# chanomele_main.net
KiCad netlist of a schematic drawn in EAGLE
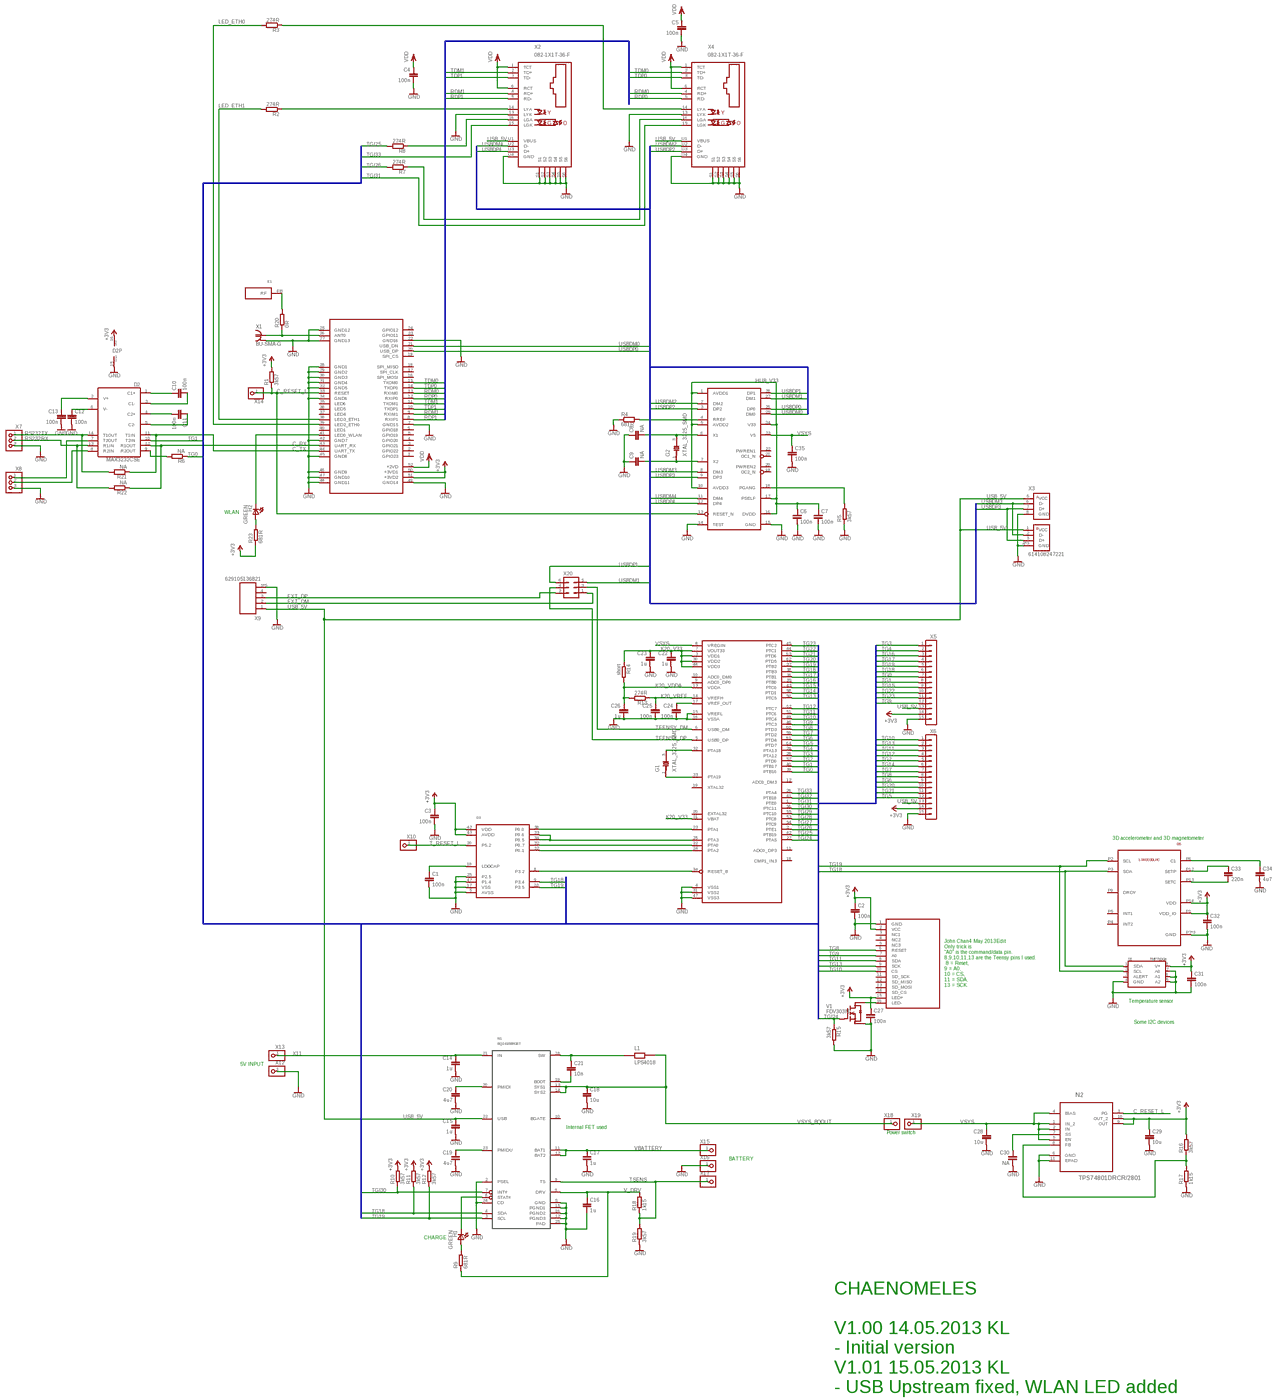
[diagram p0: schematic, sheet 1, overview]
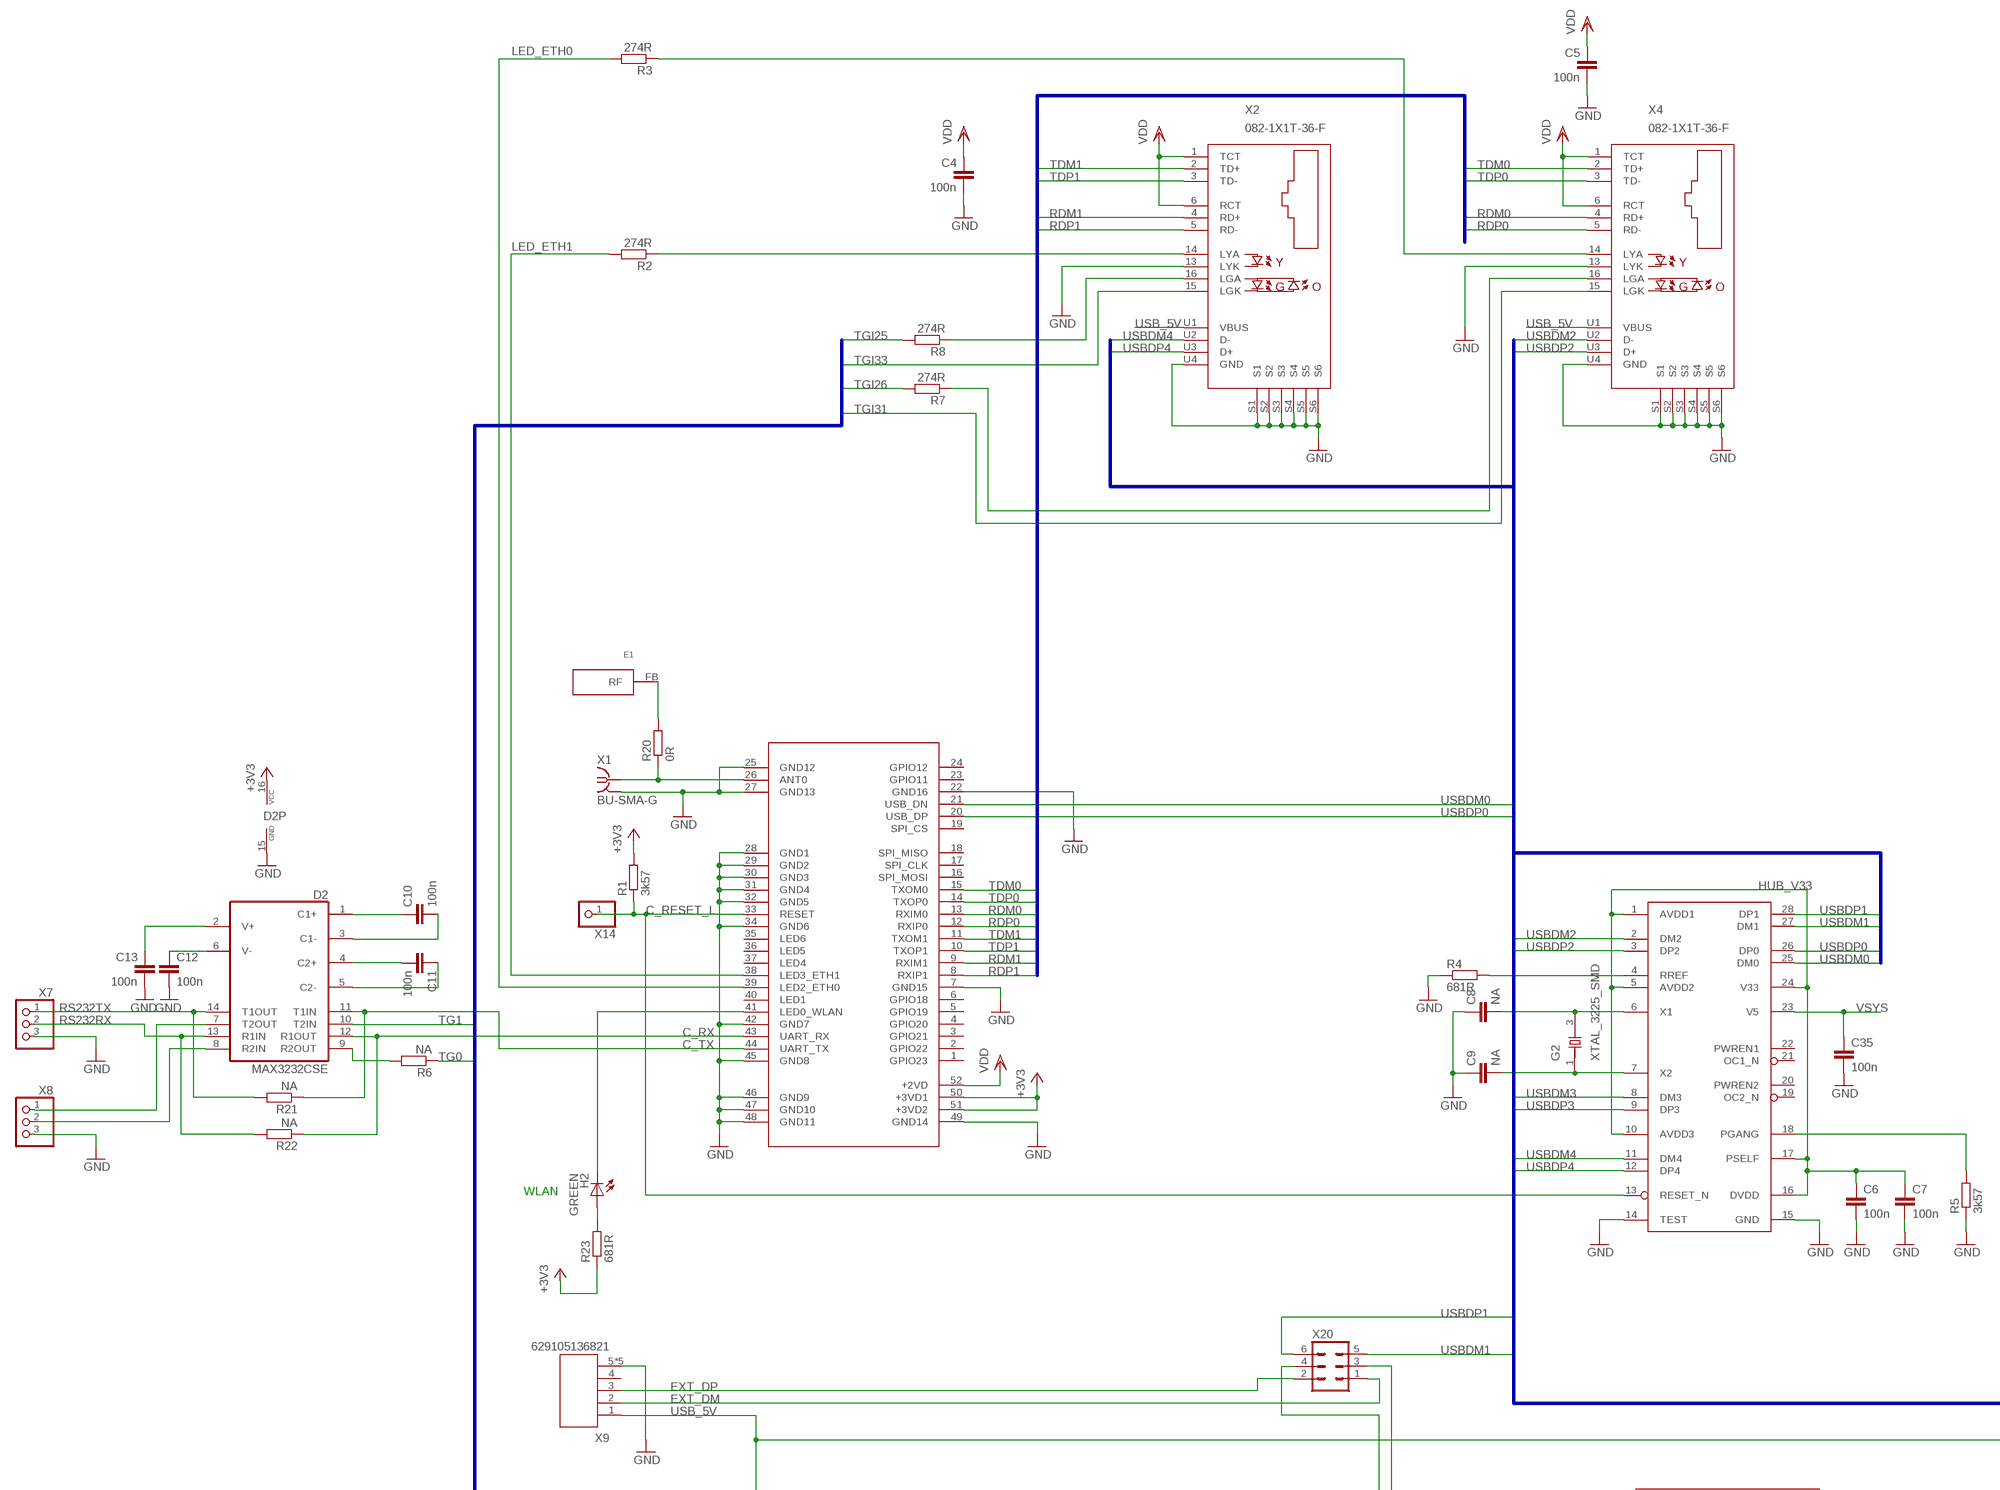
[diagram p1: schematic, sheet 1, part 1 of 4]
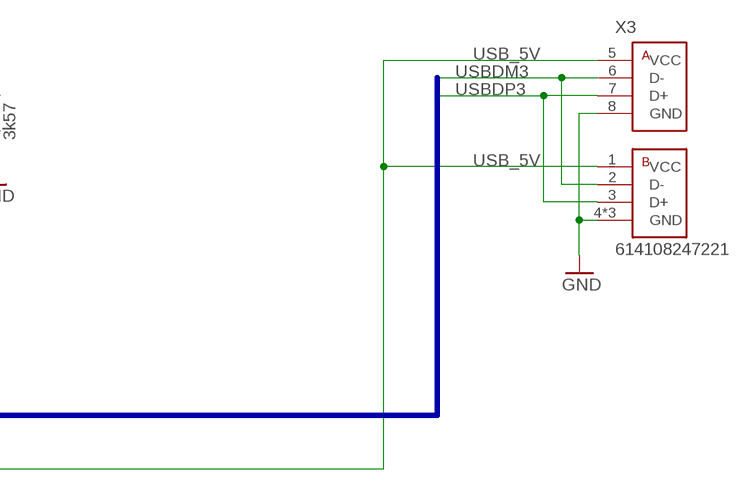
[diagram p2: schematic, sheet 1, part 2 of 4]
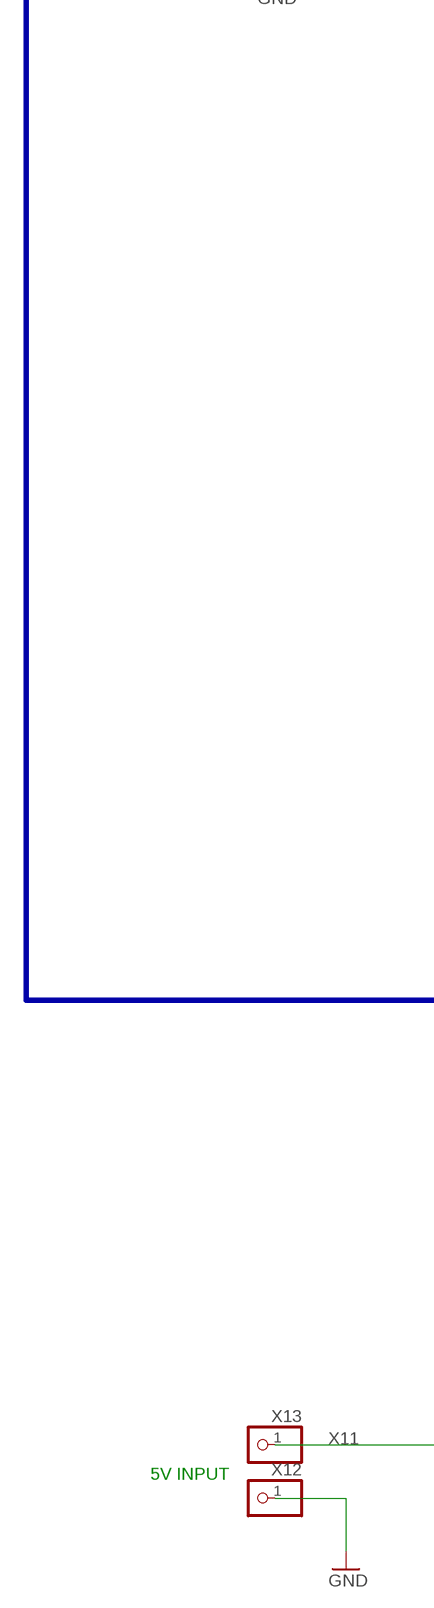
[diagram p3: schematic, sheet 1, part 3 of 4]
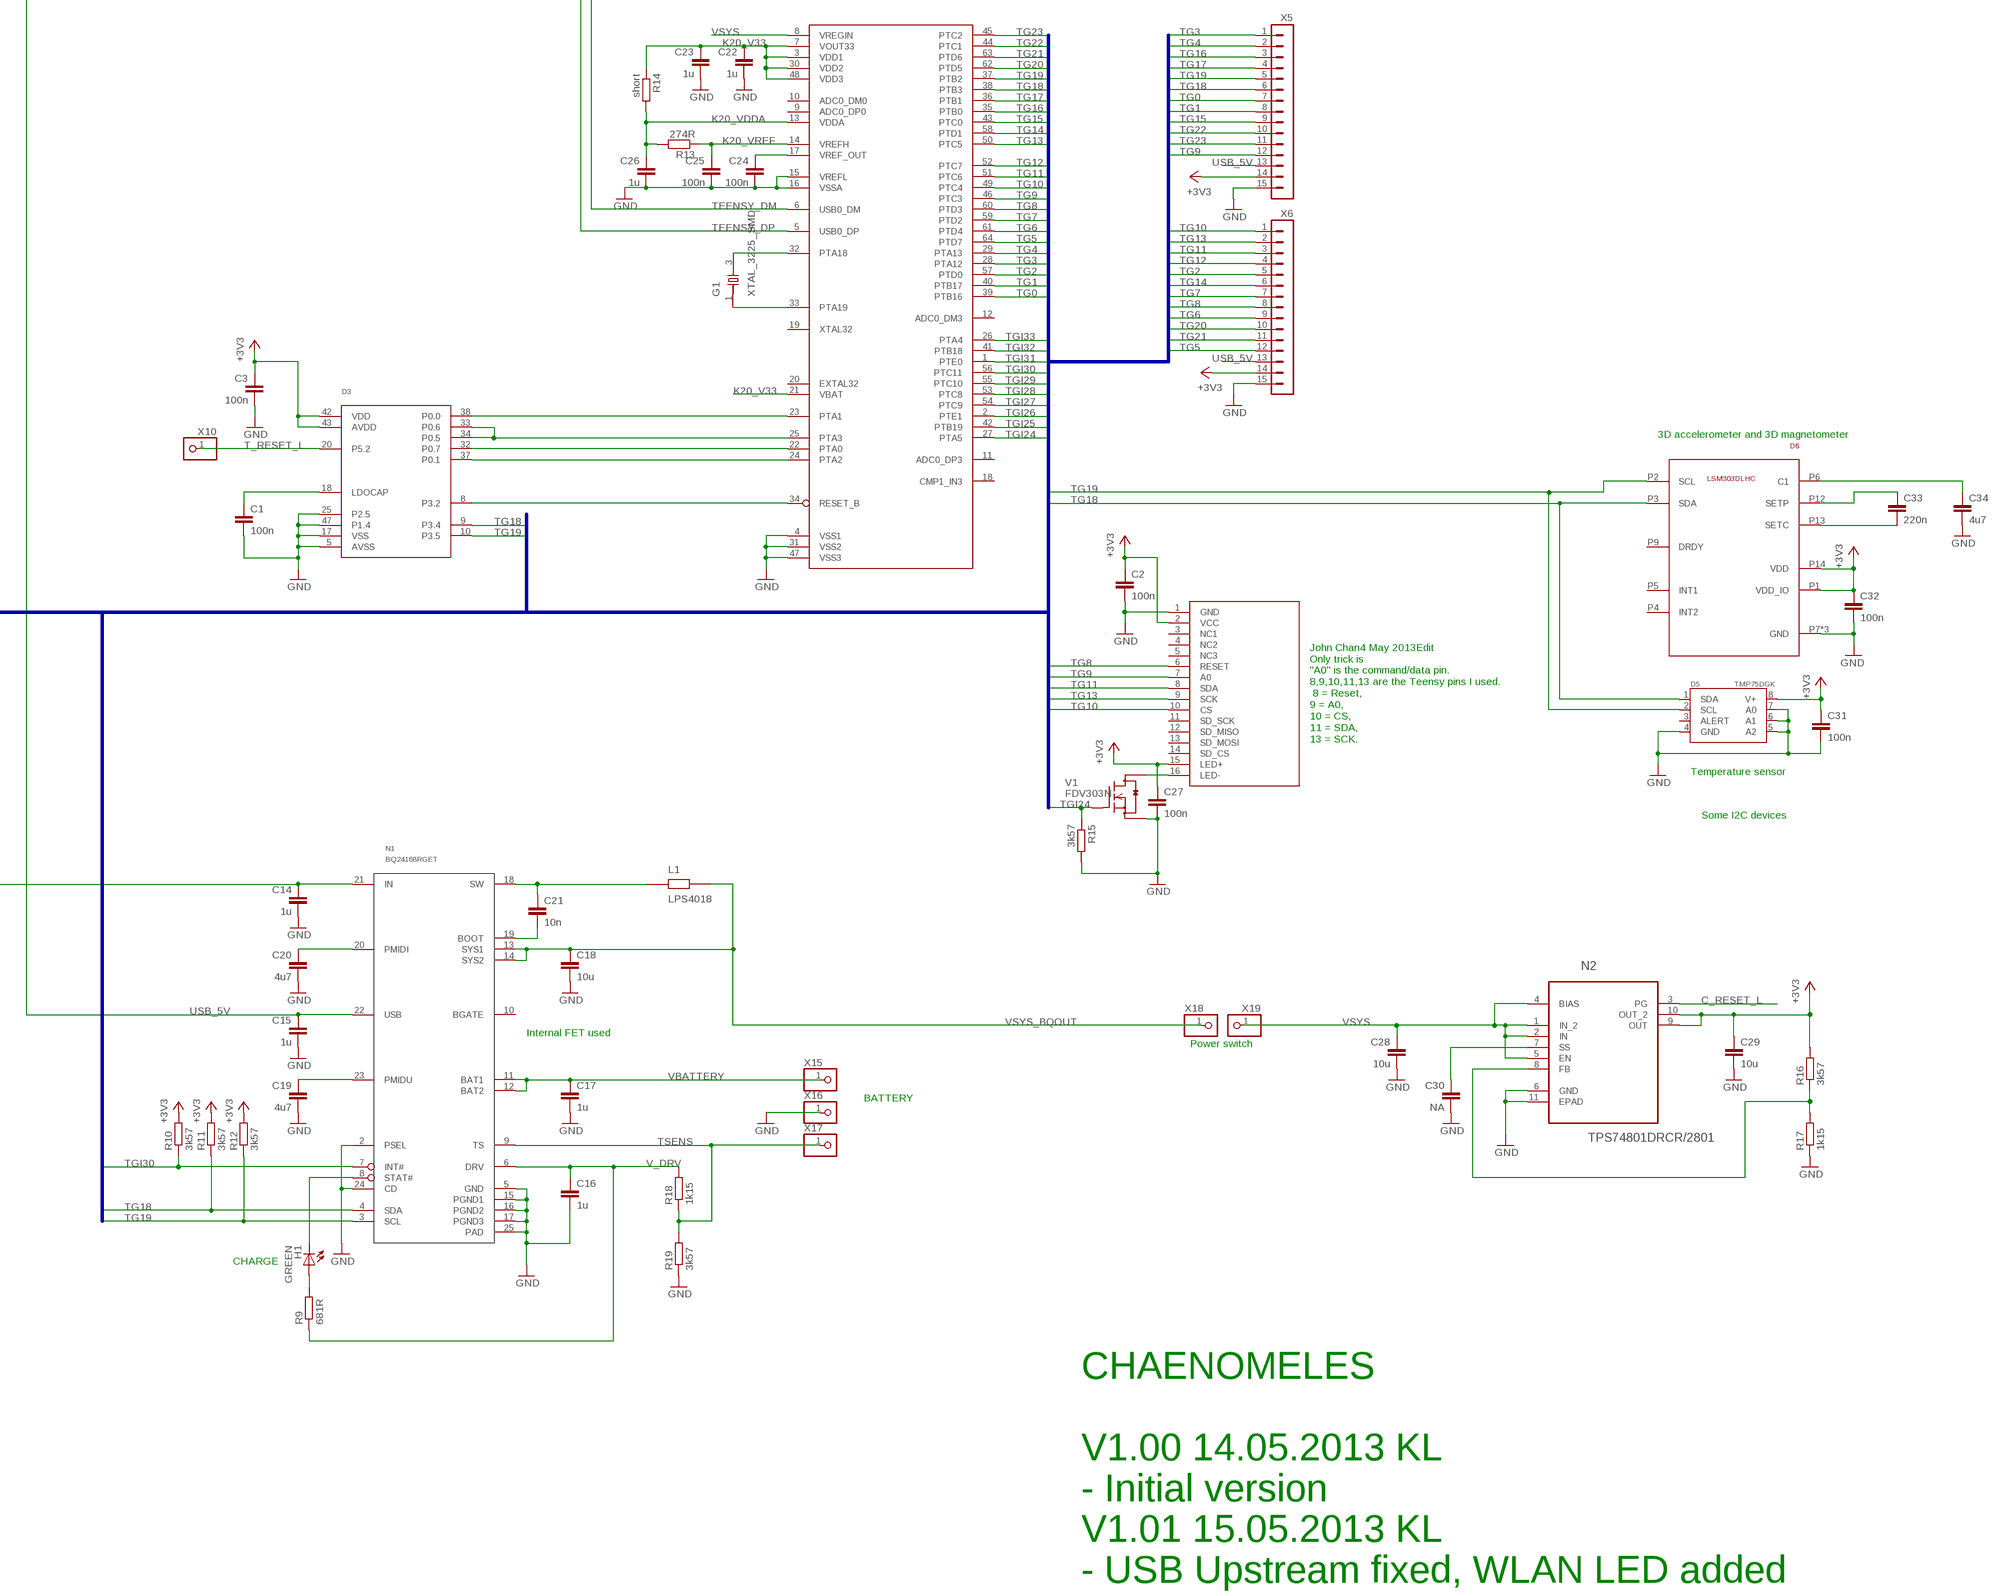
[diagram p4: schematic, sheet 1, part 4 of 4]

(export (version "E")
  (design (tool "Eeschema 10.0.6"))
  (components
    (comp (ref "A1")
      (value "CARAMBOLA2")
      (footprint "eagle-import:CARAMBOLA1")
      (libsource (lib "eagle-import") (part "CARAMBOLA2"))
    )
    (comp (ref "A2")
      (value "TFT18")
      (footprint "eagle-import:TFT18")
      (libsource (lib "eagle-import") (part "TFT18"))
    )
    (comp (ref "C1")
      (value "100n")
      (footprint "eagle-import:C0402")
      (libsource (lib "eagle-import") (part "C-EUC0402"))
    )
    (comp (ref "C2")
      (value "100n")
      (footprint "eagle-import:C0402")
      (libsource (lib "eagle-import") (part "C-EUC0402"))
    )
    (comp (ref "C3")
      (value "100n")
      (footprint "eagle-import:C0402")
      (libsource (lib "eagle-import") (part "C-EUC0402"))
    )
    (comp (ref "C4")
      (value "100n")
      (footprint "eagle-import:C0402")
      (libsource (lib "eagle-import") (part "C-EUC0402"))
    )
    (comp (ref "C5")
      (value "100n")
      (footprint "eagle-import:C0402")
      (libsource (lib "eagle-import") (part "C-EUC0402"))
    )
    (comp (ref "C6")
      (value "100n")
      (footprint "eagle-import:C0402")
      (libsource (lib "eagle-import") (part "C-EUC0402"))
    )
    (comp (ref "C7")
      (value "100n")
      (footprint "eagle-import:C0402")
      (libsource (lib "eagle-import") (part "C-EUC0402"))
    )
    (comp (ref "C8")
      (value "NA")
      (footprint "eagle-import:C0402")
      (libsource (lib "eagle-import") (part "C-EUC0402"))
    )
    (comp (ref "C9")
      (value "NA")
      (footprint "eagle-import:C0402")
      (libsource (lib "eagle-import") (part "C-EUC0402"))
    )
    (comp (ref "C10")
      (value "100n")
      (footprint "eagle-import:C0402")
      (libsource (lib "eagle-import") (part "C-EUC0402"))
    )
    (comp (ref "C11")
      (value "100n")
      (footprint "eagle-import:C0402")
      (libsource (lib "eagle-import") (part "C-EUC0402"))
    )
    (comp (ref "C12")
      (value "100n")
      (footprint "eagle-import:C0402")
      (libsource (lib "eagle-import") (part "C-EUC0402"))
    )
    (comp (ref "C13")
      (value "100n")
      (footprint "eagle-import:C0402")
      (libsource (lib "eagle-import") (part "C-EUC0402"))
    )
    (comp (ref "C14")
      (value "1u")
      (footprint "eagle-import:C0603")
      (libsource (lib "eagle-import") (part "C-EUC0603"))
    )
    (comp (ref "C15")
      (value "1u")
      (footprint "eagle-import:C0603")
      (libsource (lib "eagle-import") (part "C-EUC0603"))
    )
    (comp (ref "C16")
      (value "1u")
      (footprint "eagle-import:C0603")
      (libsource (lib "eagle-import") (part "C-EUC0603"))
    )
    (comp (ref "C17")
      (value "1u")
      (footprint "eagle-import:C0603")
      (libsource (lib "eagle-import") (part "C-EUC0603"))
    )
    (comp (ref "C18")
      (value "10u")
      (footprint "eagle-import:C0805")
      (libsource (lib "eagle-import") (part "C-EUC0805"))
    )
    (comp (ref "C19")
      (value "4u7")
      (footprint "eagle-import:C0805")
      (libsource (lib "eagle-import") (part "C-EUC0805"))
    )
    (comp (ref "C20")
      (value "4u7")
      (footprint "eagle-import:C0805")
      (libsource (lib "eagle-import") (part "C-EUC0805"))
    )
    (comp (ref "C21")
      (value "10n")
      (footprint "eagle-import:C0402")
      (libsource (lib "eagle-import") (part "C-EUC0402"))
    )
    (comp (ref "C22")
      (value "1u")
      (footprint "eagle-import:C0603")
      (libsource (lib "eagle-import") (part "C-EUC0603"))
    )
    (comp (ref "C23")
      (value "1u")
      (footprint "eagle-import:C0603")
      (libsource (lib "eagle-import") (part "C-EUC0603"))
    )
    (comp (ref "C24")
      (value "100n")
      (footprint "eagle-import:C0402")
      (libsource (lib "eagle-import") (part "C-EUC0402"))
    )
    (comp (ref "C25")
      (value "100n")
      (footprint "eagle-import:C0402")
      (libsource (lib "eagle-import") (part "C-EUC0402"))
    )
    (comp (ref "C26")
      (value "1u")
      (footprint "eagle-import:C0603")
      (libsource (lib "eagle-import") (part "C-EUC0603"))
    )
    (comp (ref "C27")
      (value "100n")
      (footprint "eagle-import:C0402")
      (libsource (lib "eagle-import") (part "C-EUC0402"))
    )
    (comp (ref "C28")
      (value "10u")
      (footprint "eagle-import:C0805")
      (libsource (lib "eagle-import") (part "C-EUC0805"))
    )
    (comp (ref "C29")
      (value "10u")
      (footprint "eagle-import:C0805")
      (libsource (lib "eagle-import") (part "C-EUC0805"))
    )
    (comp (ref "C30")
      (value "NA")
      (footprint "eagle-import:C0402")
      (libsource (lib "eagle-import") (part "C-EUC0402"))
    )
    (comp (ref "C31")
      (value "100n")
      (footprint "eagle-import:C0402")
      (libsource (lib "eagle-import") (part "C-EUC0402"))
    )
    (comp (ref "C32")
      (value "100n")
      (footprint "eagle-import:C0402")
      (libsource (lib "eagle-import") (part "C-EUC0402"))
    )
    (comp (ref "C33")
      (value "220n")
      (footprint "eagle-import:C0402")
      (libsource (lib "eagle-import") (part "C-EUC0402"))
    )
    (comp (ref "C34")
      (value "4u7")
      (footprint "eagle-import:C0805")
      (libsource (lib "eagle-import") (part "C-EUC0805"))
    )
    (comp (ref "C35")
      (value "100n")
      (footprint "eagle-import:C0402")
      (libsource (lib "eagle-import") (part "C-EUC0402"))
    )
    (comp (ref "D1")
      (value "MK20DX128VLH5")
      (footprint "eagle-import:FREESCALE_64_LQFP")
      (libsource (lib "eagle-import") (part "MK20DX128VLH5"))
    )
    (comp (ref "D2")
      (value "MAX3232CSE")
      (footprint "eagle-import:SO16")
      (libsource (lib "eagle-import") (part "MAX3232SEC"))
    )
    (comp (ref "D3")
      (value "MINI54LAN")
      (footprint "eagle-import:LQFP48-7X7")
      (libsource (lib "eagle-import") (part "MINI54LAN"))
    )
    (comp (ref "D4")
      (value "GL850G")
      (footprint "eagle-import:SSOP28DB")
      (libsource (lib "eagle-import") (part "GL850G"))
    )
    (comp (ref "D5")
      (value "TMP75DGK")
      (footprint "eagle-import:MSOP8")
      (libsource (lib "eagle-import") (part "TMP75DGK"))
    )
    (comp (ref "D6")
      (value "LSM303DLHC")
      (footprint "eagle-import:LGA_3X5X1_14L")
      (libsource (lib "eagle-import") (part "LSM303DLHC"))
    )
    (comp (ref "E1")
      (value "SMD_ANT_2.4GHZ")
      (footprint "eagle-import:2.4GHZ_SMD_ANTENNA")
      (libsource (lib "eagle-import") (part "SMD_ANT_2.4GHZ"))
    )
    (comp (ref "G1")
      (value "XTAL_3225_SMD")
      (footprint "eagle-import:X_3225")
      (libsource (lib "eagle-import") (part "XTAL_3225_SMD"))
    )
    (comp (ref "G2")
      (value "XTAL_3225_SMD")
      (footprint "eagle-import:X_3225")
      (libsource (lib "eagle-import") (part "XTAL_3225_SMD"))
    )
    (comp (ref "H1")
      (value "GREEN")
      (footprint "eagle-import:CHIP-LED0603")
      (libsource (lib "eagle-import") (part "LEDCHIP-LED0603"))
    )
    (comp (ref "H2")
      (value "GREEN")
      (footprint "eagle-import:CHIP-LED0603")
      (libsource (lib "eagle-import") (part "LEDCHIP-LED0603"))
    )
    (comp (ref "L1")
      (value "LPS4018")
      (footprint "eagle-import:LPS4018")
      (libsource (lib "eagle-import") (part "LPS4018"))
    )
    (comp (ref "N1")
      (value "BQ24168RGET")
      (footprint "eagle-import:QFN50P400X400X100-25N")
      (libsource (lib "eagle-import") (part "BQ24168RGET"))
    )
    (comp (ref "N2")
      (value "TPS74801DRCR/2801")
      (footprint "eagle-import:SON50P300X300X100-11N")
      (libsource (lib "eagle-import") (part "TPS74801DRCR/2801"))
    )
    (comp (ref "R1")
      (value "3k57")
      (footprint "eagle-import:R0402")
      (libsource (lib "eagle-import") (part "R-EU_R0402"))
    )
    (comp (ref "R2")
      (value "274R")
      (footprint "eagle-import:R0402")
      (libsource (lib "eagle-import") (part "R-EU_R0402"))
    )
    (comp (ref "R3")
      (value "274R")
      (footprint "eagle-import:R0402")
      (libsource (lib "eagle-import") (part "R-EU_R0402"))
    )
    (comp (ref "R4")
      (value "681R")
      (footprint "eagle-import:R0402")
      (libsource (lib "eagle-import") (part "R-EU_R0402"))
    )
    (comp (ref "R5")
      (value "3k57")
      (footprint "eagle-import:R0402")
      (libsource (lib "eagle-import") (part "R-EU_R0402"))
    )
    (comp (ref "R6")
      (value "NA")
      (footprint "eagle-import:R0402")
      (libsource (lib "eagle-import") (part "R-EU_R0402"))
    )
    (comp (ref "R7")
      (value "274R")
      (footprint "eagle-import:R0402")
      (libsource (lib "eagle-import") (part "R-EU_R0402"))
    )
    (comp (ref "R8")
      (value "274R")
      (footprint "eagle-import:R0402")
      (libsource (lib "eagle-import") (part "R-EU_R0402"))
    )
    (comp (ref "R9")
      (value "681R")
      (footprint "eagle-import:R0402")
      (libsource (lib "eagle-import") (part "R-EU_R0402"))
    )
    (comp (ref "R10")
      (value "3k57")
      (footprint "eagle-import:R0402")
      (libsource (lib "eagle-import") (part "R-EU_R0402"))
    )
    (comp (ref "R11")
      (value "3k57")
      (footprint "eagle-import:R0402")
      (libsource (lib "eagle-import") (part "R-EU_R0402"))
    )
    (comp (ref "R12")
      (value "3k57")
      (footprint "eagle-import:R0402")
      (libsource (lib "eagle-import") (part "R-EU_R0402"))
    )
    (comp (ref "R13")
      (value "274R")
      (footprint "eagle-import:R0402")
      (libsource (lib "eagle-import") (part "R-EU_R0402"))
    )
    (comp (ref "R14")
      (value "short")
      (footprint "eagle-import:R0402")
      (libsource (lib "eagle-import") (part "R-EU_R0402"))
    )
    (comp (ref "R15")
      (value "3k57")
      (footprint "eagle-import:R0402")
      (libsource (lib "eagle-import") (part "R-EU_R0402"))
    )
    (comp (ref "R16")
      (value "3k57")
      (footprint "eagle-import:R0402")
      (libsource (lib "eagle-import") (part "R-EU_R0402"))
    )
    (comp (ref "R17")
      (value "1k15")
      (footprint "eagle-import:R0402")
      (libsource (lib "eagle-import") (part "R-EU_R0402"))
    )
    (comp (ref "R18")
      (value "1k15")
      (footprint "eagle-import:R0402")
      (libsource (lib "eagle-import") (part "R-EU_R0402"))
    )
    (comp (ref "R19")
      (value "3k57")
      (footprint "eagle-import:R0402")
      (libsource (lib "eagle-import") (part "R-EU_R0402"))
    )
    (comp (ref "R20")
      (value "0R")
      (footprint "eagle-import:R0402")
      (libsource (lib "eagle-import") (part "R-EU_R0402"))
    )
    (comp (ref "R21")
      (value "NA")
      (footprint "eagle-import:R0402")
      (libsource (lib "eagle-import") (part "R-EU_R0402"))
    )
    (comp (ref "R22")
      (value "NA")
      (footprint "eagle-import:R0402")
      (libsource (lib "eagle-import") (part "R-EU_R0402"))
    )
    (comp (ref "R23")
      (value "681R")
      (footprint "eagle-import:R0402")
      (libsource (lib "eagle-import") (part "R-EU_R0402"))
    )
    (comp (ref "V1")
      (value "FDV303N")
      (footprint "eagle-import:SOT23")
      (libsource (lib "eagle-import") (part "FDV303N"))
    )
    (comp (ref "X1")
      (value "BU-SMA-G")
      (footprint "eagle-import:BU-SMA-G")
      (libsource (lib "eagle-import") (part "BU-SMA-G"))
    )
    (comp (ref "X2")
      (value "082-1X1T-36-F")
      (footprint "eagle-import:0821-1X1T-36-F")
      (libsource (lib "eagle-import") (part "082-1X1T-36-F"))
    )
    (comp (ref "X3")
      (value "614108247221")
      (footprint "eagle-import:614108247221")
      (libsource (lib "eagle-import") (part "614108247221"))
    )
    (comp (ref "X4")
      (value "082-1X1T-36-F")
      (footprint "eagle-import:0821-1X1T-36-F")
      (libsource (lib "eagle-import") (part "082-1X1T-36-F"))
    )
    (comp (ref "X5")
      (value "PIIKKIRIMA-15")
      (footprint "eagle-import:PIIKKIRIMA-15")
      (libsource (lib "eagle-import") (part "PIIKKIRIMA-15"))
    )
    (comp (ref "X6")
      (value "PIIKKIRIMA-15")
      (footprint "eagle-import:PIIKKIRIMA-15")
      (libsource (lib "eagle-import") (part "PIIKKIRIMA-15"))
    )
    (comp (ref "X7")
      (value "PINHD-1X3/90")
      (footprint "eagle-import:1X03_90")
      (libsource (lib "eagle-import") (part "PINHD-1X3/90"))
    )
    (comp (ref "X8")
      (value "PINHD-1X3/90")
      (footprint "eagle-import:1X03_90")
      (libsource (lib "eagle-import") (part "PINHD-1X3/90"))
    )
    (comp (ref "X9")
      (value "629105136821")
      (footprint "eagle-import:629105136821")
      (libsource (lib "eagle-import") (part "629105136821"))
    )
    (comp (ref "X10")
      (value "PINHD-1X1")
      (footprint "eagle-import:1X01")
      (libsource (lib "eagle-import") (part "PINHD-1X1"))
    )
    (comp (ref "X12")
      (value "PINHD-1X1")
      (footprint "eagle-import:1X01")
      (libsource (lib "eagle-import") (part "PINHD-1X1"))
    )
    (comp (ref "X13")
      (value "PINHD-1X1")
      (footprint "eagle-import:1X01")
      (libsource (lib "eagle-import") (part "PINHD-1X1"))
    )
    (comp (ref "X14")
      (value "PINHD-1X1")
      (footprint "eagle-import:1X01")
      (libsource (lib "eagle-import") (part "PINHD-1X1"))
    )
    (comp (ref "X15")
      (value "PINHD-1X1")
      (footprint "eagle-import:1X01")
      (libsource (lib "eagle-import") (part "PINHD-1X1"))
    )
    (comp (ref "X16")
      (value "PINHD-1X1")
      (footprint "eagle-import:1X01")
      (libsource (lib "eagle-import") (part "PINHD-1X1"))
    )
    (comp (ref "X17")
      (value "PINHD-1X1")
      (footprint "eagle-import:1X01")
      (libsource (lib "eagle-import") (part "PINHD-1X1"))
    )
    (comp (ref "X18")
      (value "PINHD-1X1")
      (footprint "eagle-import:1X01")
      (libsource (lib "eagle-import") (part "PINHD-1X1"))
    )
    (comp (ref "X19")
      (value "PINHD-1X1")
      (footprint "eagle-import:1X01")
      (libsource (lib "eagle-import") (part "PINHD-1X1"))
    )
    (comp (ref "X20")
      (value "MA03-2")
      (footprint "eagle-import:MA03-2")
      (libsource (lib "eagle-import") (part "MA03-2"))
    )
  )
  (nets
    (net (code "1") (name "+3V3") (class "Default")
      (node (ref "A1") (pin "50") (pinfunction "+3VD1_50") (pintype "bidirectional"))
      (node (ref "A1") (pin "51") (pinfunction "+3VD2_51") (pintype "bidirectional"))
      (node (ref "A2") (pin "15") (pinfunction "LED+_15") (pintype "bidirectional"))
      (node (ref "A2") (pin "2") (pinfunction "VCC_2") (pintype "bidirectional"))
      (node (ref "C2") (pin "1") (pinfunction "1_1") (pintype "passive"))
      (node (ref "C27") (pin "1") (pinfunction "1_1") (pintype "passive"))
      (node (ref "C29") (pin "1") (pinfunction "1_1") (pintype "passive"))
      (node (ref "C3") (pin "1") (pinfunction "1_1") (pintype "passive"))
      (node (ref "C31") (pin "1") (pinfunction "1_1") (pintype "passive"))
      (node (ref "C32") (pin "1") (pinfunction "1_1") (pintype "passive"))
      (node (ref "D2") (pin "16") (pinfunction "VCC_16") (pintype "power_in"))
      (node (ref "D3") (pin "42") (pinfunction "VDD_42") (pintype "bidirectional"))
      (node (ref "D3") (pin "43") (pinfunction "AVDD_43") (pintype "bidirectional"))
      (node (ref "D5") (pin "8") (pinfunction "V+_8") (pintype "bidirectional"))
      (node (ref "D6") (pin "P1") (pinfunction "VDD_IO_P1") (pintype "bidirectional"))
      (node (ref "D6") (pin "P14") (pinfunction "VDD_P14") (pintype "bidirectional"))
      (node (ref "N2") (pin "10") (pinfunction "OUT_2_10") (pintype "output"))
      (node (ref "N2") (pin "9") (pinfunction "OUT_9") (pintype "output"))
      (node (ref "R1") (pin "2") (pinfunction "2_2") (pintype "passive"))
      (node (ref "R10") (pin "2") (pinfunction "2_2") (pintype "passive"))
      (node (ref "R11") (pin "2") (pinfunction "2_2") (pintype "passive"))
      (node (ref "R12") (pin "2") (pinfunction "2_2") (pintype "passive"))
      (node (ref "R16") (pin "2") (pinfunction "2_2") (pintype "passive"))
      (node (ref "R23") (pin "1") (pinfunction "1_1") (pintype "passive"))
      (node (ref "X5") (pin "14") (pinfunction "14_14") (pintype "passive"))
      (node (ref "X6") (pin "14") (pinfunction "14_14") (pintype "passive"))
    )
    (net (code "2") (name "/C_RESET_L") (class "Default")
      (node (ref "A1") (pin "33") (pinfunction "RESET_33") (pintype "bidirectional"))
      (node (ref "D4") (pin "13") (pinfunction "RESET_N_13") (pintype "bidirectional"))
      (node (ref "N2") (pin "3") (pinfunction "PG_3") (pintype "output"))
      (node (ref "R1") (pin "1") (pinfunction "1_1") (pintype "passive"))
      (node (ref "X14") (pin "1") (pinfunction "1_1") (pintype "passive"))
    )
    (net (code "3") (name "/C_RX") (class "Default")
      (node (ref "A1") (pin "43") (pinfunction "UART_RX_43") (pintype "bidirectional"))
      (node (ref "D2") (pin "12") (pinfunction "R1OUT_12") (pintype "output"))
      (node (ref "R22") (pin "1") (pinfunction "1_1") (pintype "passive"))
    )
    (net (code "4") (name "/C_TX") (class "Default")
      (node (ref "A1") (pin "44") (pinfunction "UART_TX_44") (pintype "bidirectional"))
      (node (ref "D2") (pin "11") (pinfunction "T1IN_11") (pintype "input"))
      (node (ref "R21") (pin "1") (pinfunction "1_1") (pintype "passive"))
    )
    (net (code "5") (name "/EXT_DM") (class "Default")
      (node (ref "X20") (pin "1") (pinfunction "1_1") (pintype "passive"))
      (node (ref "X9") (pin "2") (pinfunction "2_2") (pintype "passive"))
    )
    (net (code "6") (name "/EXT_DP") (class "Default")
      (node (ref "X20") (pin "2") (pinfunction "2_2") (pintype "passive"))
      (node (ref "X9") (pin "3") (pinfunction "3_3") (pintype "passive"))
    )
    (net (code "7") (name "/HUB_V33") (class "Default")
      (node (ref "C6") (pin "1") (pinfunction "1_1") (pintype "passive"))
      (node (ref "C7") (pin "1") (pinfunction "1_1") (pintype "passive"))
      (node (ref "D4") (pin "1") (pinfunction "AVDD1_1") (pintype "bidirectional"))
      (node (ref "D4") (pin "10") (pinfunction "AVDD3_10") (pintype "bidirectional"))
      (node (ref "D4") (pin "16") (pinfunction "DVDD_16") (pintype "bidirectional"))
      (node (ref "D4") (pin "17") (pinfunction "PSELF_17") (pintype "bidirectional"))
      (node (ref "D4") (pin "24") (pinfunction "V33_24") (pintype "bidirectional"))
      (node (ref "D4") (pin "5") (pinfunction "AVDD2_5") (pintype "bidirectional"))
    )
    (net (code "8") (name "/K20_V33") (class "Default")
      (node (ref "C22") (pin "1") (pinfunction "1_1") (pintype "passive"))
      (node (ref "C23") (pin "1") (pinfunction "1_1") (pintype "passive"))
      (node (ref "D1") (pin "21") (pinfunction "VBAT_21") (pintype "bidirectional"))
      (node (ref "D1") (pin "3") (pinfunction "VDD1_3") (pintype "bidirectional"))
      (node (ref "D1") (pin "30") (pinfunction "VDD2_30") (pintype "bidirectional"))
      (node (ref "D1") (pin "48") (pinfunction "VDD3_48") (pintype "bidirectional"))
      (node (ref "D1") (pin "7") (pinfunction "VOUT33_7") (pintype "bidirectional"))
      (node (ref "R14") (pin "1") (pinfunction "1_1") (pintype "passive"))
    )
    (net (code "9") (name "/K20_VDDA") (class "Default")
      (node (ref "C26") (pin "1") (pinfunction "1_1") (pintype "passive"))
      (node (ref "D1") (pin "13") (pinfunction "VDDA_13") (pintype "bidirectional"))
      (node (ref "R13") (pin "2") (pinfunction "2_2") (pintype "passive"))
      (node (ref "R14") (pin "2") (pinfunction "2_2") (pintype "passive"))
    )
    (net (code "10") (name "/K20_VREF") (class "Default")
      (node (ref "C25") (pin "1") (pinfunction "1_1") (pintype "passive"))
      (node (ref "D1") (pin "14") (pinfunction "VREFH_14") (pintype "bidirectional"))
      (node (ref "R13") (pin "1") (pinfunction "1_1") (pintype "passive"))
    )
    (net (code "11") (name "/LED_ETH0") (class "Default")
      (node (ref "A1") (pin "39") (pinfunction "LED2_ETH0_39") (pintype "bidirectional"))
      (node (ref "R3") (pin "2") (pinfunction "2_2") (pintype "passive"))
    )
    (net (code "12") (name "/LED_ETH1") (class "Default")
      (node (ref "A1") (pin "38") (pinfunction "LED3_ETH1_38") (pintype "bidirectional"))
      (node (ref "R2") (pin "2") (pinfunction "2_2") (pintype "passive"))
    )
    (net (code "13") (name "/RDM0") (class "Default")
      (node (ref "A1") (pin "13") (pinfunction "RXIM0_13") (pintype "bidirectional"))
      (node (ref "X4") (pin "4") (pinfunction "RD+_4") (pintype "bidirectional"))
    )
    (net (code "14") (name "/RDM1") (class "Default")
      (node (ref "A1") (pin "9") (pinfunction "RXIM1_9") (pintype "bidirectional"))
      (node (ref "X2") (pin "4") (pinfunction "RD+_4") (pintype "bidirectional"))
    )
    (net (code "15") (name "/RDP0") (class "Default")
      (node (ref "A1") (pin "12") (pinfunction "RXIP0_12") (pintype "bidirectional"))
      (node (ref "X4") (pin "5") (pinfunction "RD-_5") (pintype "bidirectional"))
    )
    (net (code "16") (name "/RDP1") (class "Default")
      (node (ref "A1") (pin "8") (pinfunction "RXIP1_8") (pintype "bidirectional"))
      (node (ref "X2") (pin "5") (pinfunction "RD-_5") (pintype "bidirectional"))
    )
    (net (code "17") (name "/RS232RX") (class "Default")
      (node (ref "D2") (pin "13") (pinfunction "R1IN_13") (pintype "input"))
      (node (ref "R22") (pin "2") (pinfunction "2_2") (pintype "passive"))
      (node (ref "X7") (pin "2") (pinfunction "2_2") (pintype "passive"))
    )
    (net (code "18") (name "/RS232TX") (class "Default")
      (node (ref "D2") (pin "14") (pinfunction "T1OUT_14") (pintype "output"))
      (node (ref "R21") (pin "2") (pinfunction "2_2") (pintype "passive"))
      (node (ref "X7") (pin "1") (pinfunction "1_1") (pintype "passive"))
    )
    (net (code "19") (name "/TDM0") (class "Default")
      (node (ref "A1") (pin "15") (pinfunction "TXOM0_15") (pintype "bidirectional"))
      (node (ref "X4") (pin "2") (pinfunction "TD+_2") (pintype "bidirectional"))
    )
    (net (code "20") (name "/TDM1") (class "Default")
      (node (ref "A1") (pin "11") (pinfunction "TXOM1_11") (pintype "bidirectional"))
      (node (ref "X2") (pin "2") (pinfunction "TD+_2") (pintype "bidirectional"))
    )
    (net (code "21") (name "/TDP0") (class "Default")
      (node (ref "A1") (pin "14") (pinfunction "TXOP0_14") (pintype "bidirectional"))
      (node (ref "X4") (pin "3") (pinfunction "TD-_3") (pintype "bidirectional"))
    )
    (net (code "22") (name "/TDP1") (class "Default")
      (node (ref "A1") (pin "10") (pinfunction "TXOP1_10") (pintype "bidirectional"))
      (node (ref "X2") (pin "3") (pinfunction "TD-_3") (pintype "bidirectional"))
    )
    (net (code "23") (name "/TEENSY_DM") (class "Default")
      (node (ref "D1") (pin "6") (pinfunction "USB0_DM_6") (pintype "bidirectional"))
      (node (ref "X20") (pin "3") (pinfunction "3_3") (pintype "passive"))
    )
    (net (code "24") (name "/TEENSY_DP") (class "Default")
      (node (ref "D1") (pin "5") (pinfunction "USB0_DP_5") (pintype "bidirectional"))
      (node (ref "X20") (pin "4") (pinfunction "4_4") (pintype "passive"))
    )
    (net (code "25") (name "/TG0") (class "Default")
      (node (ref "D1") (pin "39") (pinfunction "PTB16_39") (pintype "bidirectional"))
      (node (ref "R6") (pin "1") (pinfunction "1_1") (pintype "passive"))
      (node (ref "X5") (pin "7") (pinfunction "7_7") (pintype "passive"))
    )
    (net (code "26") (name "/TG1") (class "Default")
      (node (ref "D1") (pin "40") (pinfunction "PTB17_40") (pintype "bidirectional"))
      (node (ref "D2") (pin "10") (pinfunction "T2IN_10") (pintype "input"))
      (node (ref "X5") (pin "8") (pinfunction "8_8") (pintype "passive"))
    )
    (net (code "27") (name "/TG2") (class "Default")
      (node (ref "D1") (pin "57") (pinfunction "PTD0_57") (pintype "bidirectional"))
      (node (ref "X6") (pin "5") (pinfunction "5_5") (pintype "passive"))
    )
    (net (code "28") (name "/TG3") (class "Default")
      (node (ref "D1") (pin "28") (pinfunction "PTA12_28") (pintype "bidirectional"))
      (node (ref "X5") (pin "1") (pinfunction "1_1") (pintype "passive"))
    )
    (net (code "29") (name "/TG4") (class "Default")
      (node (ref "D1") (pin "29") (pinfunction "PTA13_29") (pintype "bidirectional"))
      (node (ref "X5") (pin "2") (pinfunction "2_2") (pintype "passive"))
    )
    (net (code "30") (name "/TG5") (class "Default")
      (node (ref "D1") (pin "64") (pinfunction "PTD7_64") (pintype "bidirectional"))
      (node (ref "X6") (pin "12") (pinfunction "12_12") (pintype "passive"))
    )
    (net (code "31") (name "/TG6") (class "Default")
      (node (ref "D1") (pin "61") (pinfunction "PTD4_61") (pintype "bidirectional"))
      (node (ref "X6") (pin "9") (pinfunction "9_9") (pintype "passive"))
    )
    (net (code "32") (name "/TG7") (class "Default")
      (node (ref "D1") (pin "59") (pinfunction "PTD2_59") (pintype "bidirectional"))
      (node (ref "X6") (pin "7") (pinfunction "7_7") (pintype "passive"))
    )
    (net (code "33") (name "/TG8") (class "Default")
      (node (ref "A2") (pin "6") (pinfunction "RESET_6") (pintype "bidirectional"))
      (node (ref "D1") (pin "60") (pinfunction "PTD3_60") (pintype "bidirectional"))
      (node (ref "X6") (pin "8") (pinfunction "8_8") (pintype "passive"))
    )
    (net (code "34") (name "/TG9") (class "Default")
      (node (ref "A2") (pin "7") (pinfunction "A0_7") (pintype "bidirectional"))
      (node (ref "D1") (pin "46") (pinfunction "PTC3_46") (pintype "bidirectional"))
      (node (ref "X5") (pin "12") (pinfunction "12_12") (pintype "passive"))
    )
    (net (code "35") (name "/TG10") (class "Default")
      (node (ref "A2") (pin "10") (pinfunction "CS_10") (pintype "bidirectional"))
      (node (ref "D1") (pin "49") (pinfunction "PTC4_49") (pintype "bidirectional"))
      (node (ref "X6") (pin "1") (pinfunction "1_1") (pintype "passive"))
    )
    (net (code "36") (name "/TG11") (class "Default")
      (node (ref "A2") (pin "8") (pinfunction "SDA_8") (pintype "bidirectional"))
      (node (ref "D1") (pin "51") (pinfunction "PTC6_51") (pintype "bidirectional"))
      (node (ref "X6") (pin "3") (pinfunction "3_3") (pintype "passive"))
    )
    (net (code "37") (name "/TG12") (class "Default")
      (node (ref "D1") (pin "52") (pinfunction "PTC7_52") (pintype "bidirectional"))
      (node (ref "X6") (pin "4") (pinfunction "4_4") (pintype "passive"))
    )
    (net (code "38") (name "/TG13") (class "Default")
      (node (ref "A2") (pin "9") (pinfunction "SCK_9") (pintype "bidirectional"))
      (node (ref "D1") (pin "50") (pinfunction "PTC5_50") (pintype "bidirectional"))
      (node (ref "X6") (pin "2") (pinfunction "2_2") (pintype "passive"))
    )
    (net (code "39") (name "/TG14") (class "Default")
      (node (ref "D1") (pin "58") (pinfunction "PTD1_58") (pintype "bidirectional"))
      (node (ref "X6") (pin "6") (pinfunction "6_6") (pintype "passive"))
    )
    (net (code "40") (name "/TG15") (class "Default")
      (node (ref "D1") (pin "43") (pinfunction "PTC0_43") (pintype "bidirectional"))
      (node (ref "X5") (pin "9") (pinfunction "9_9") (pintype "passive"))
    )
    (net (code "41") (name "/TG16") (class "Default")
      (node (ref "D1") (pin "35") (pinfunction "PTB0_35") (pintype "bidirectional"))
      (node (ref "X5") (pin "3") (pinfunction "3_3") (pintype "passive"))
    )
    (net (code "42") (name "/TG17") (class "Default")
      (node (ref "D1") (pin "36") (pinfunction "PTB1_36") (pintype "bidirectional"))
      (node (ref "X5") (pin "4") (pinfunction "4_4") (pintype "passive"))
    )
    (net (code "43") (name "/TG18") (class "Default")
      (node (ref "D1") (pin "38") (pinfunction "PTB3_38") (pintype "bidirectional"))
      (node (ref "D3") (pin "9") (pinfunction "P3.4_9") (pintype "bidirectional"))
      (node (ref "D5") (pin "1") (pinfunction "SDA_1") (pintype "bidirectional"))
      (node (ref "D6") (pin "P3") (pinfunction "SDA_P3") (pintype "bidirectional"))
      (node (ref "N1") (pin "4") (pinfunction "SDA_4") (pintype "bidirectional"))
      (node (ref "R11") (pin "1") (pinfunction "1_1") (pintype "passive"))
      (node (ref "X5") (pin "6") (pinfunction "6_6") (pintype "passive"))
    )
    (net (code "44") (name "/TG19") (class "Default")
      (node (ref "D1") (pin "37") (pinfunction "PTB2_37") (pintype "bidirectional"))
      (node (ref "D3") (pin "10") (pinfunction "P3.5_10") (pintype "bidirectional"))
      (node (ref "D5") (pin "2") (pinfunction "SCL_2") (pintype "bidirectional"))
      (node (ref "D6") (pin "P2") (pinfunction "SCL_P2") (pintype "bidirectional"))
      (node (ref "N1") (pin "3") (pinfunction "SCL_3") (pintype "bidirectional"))
      (node (ref "R12") (pin "1") (pinfunction "1_1") (pintype "passive"))
      (node (ref "X5") (pin "5") (pinfunction "5_5") (pintype "passive"))
    )
    (net (code "45") (name "/TG20") (class "Default")
      (node (ref "D1") (pin "62") (pinfunction "PTD5_62") (pintype "bidirectional"))
      (node (ref "X6") (pin "10") (pinfunction "10_10") (pintype "passive"))
    )
    (net (code "46") (name "/TG21") (class "Default")
      (node (ref "D1") (pin "63") (pinfunction "PTD6_63") (pintype "bidirectional"))
      (node (ref "X6") (pin "11") (pinfunction "11_11") (pintype "passive"))
    )
    (net (code "47") (name "/TG22") (class "Default")
      (node (ref "D1") (pin "44") (pinfunction "PTC1_44") (pintype "bidirectional"))
      (node (ref "X5") (pin "10") (pinfunction "10_10") (pintype "passive"))
    )
    (net (code "48") (name "/TG23") (class "Default")
      (node (ref "D1") (pin "45") (pinfunction "PTC2_45") (pintype "bidirectional"))
      (node (ref "X5") (pin "11") (pinfunction "11_11") (pintype "passive"))
    )
    (net (code "49") (name "/TGI24") (class "Default")
      (node (ref "D1") (pin "27") (pinfunction "PTA5_27") (pintype "bidirectional"))
      (node (ref "R15") (pin "1") (pinfunction "1_1") (pintype "passive"))
      (node (ref "V1") (pin "1") (pinfunction "G_1") (pintype "input"))
    )
    (net (code "50") (name "/TGI25") (class "Default")
      (node (ref "D1") (pin "42") (pinfunction "PTB19_42") (pintype "bidirectional"))
      (node (ref "R8") (pin "2") (pinfunction "2_2") (pintype "passive"))
    )
    (net (code "51") (name "/TGI26") (class "Default")
      (node (ref "D1") (pin "2") (pinfunction "PTE1_2") (pintype "bidirectional"))
      (node (ref "R7") (pin "2") (pinfunction "2_2") (pintype "passive"))
    )
    (net (code "52") (name "/TGI27") (class "Default")
      (node (ref "D1") (pin "54") (pinfunction "PTC9_54") (pintype "bidirectional"))
    )
    (net (code "53") (name "/TGI28") (class "Default")
      (node (ref "D1") (pin "53") (pinfunction "PTC8_53") (pintype "bidirectional"))
    )
    (net (code "54") (name "/TGI29") (class "Default")
      (node (ref "D1") (pin "55") (pinfunction "PTC10_55") (pintype "bidirectional"))
    )
    (net (code "55") (name "/TGI30") (class "Default")
      (node (ref "D1") (pin "56") (pinfunction "PTC11_56") (pintype "bidirectional"))
      (node (ref "N1") (pin "7") (pinfunction "INT#_7") (pintype "bidirectional"))
      (node (ref "R10") (pin "1") (pinfunction "1_1") (pintype "passive"))
    )
    (net (code "56") (name "/TGI31") (class "Default")
      (node (ref "D1") (pin "1") (pinfunction "PTE0_1") (pintype "bidirectional"))
      (node (ref "X4") (pin "15") (pinfunction "LGK_15") (pintype "bidirectional"))
    )
    (net (code "57") (name "/TGI32") (class "Default")
      (node (ref "D1") (pin "41") (pinfunction "PTB18_41") (pintype "bidirectional"))
    )
    (net (code "58") (name "/TGI33") (class "Default")
      (node (ref "D1") (pin "26") (pinfunction "PTA4_26") (pintype "bidirectional"))
      (node (ref "X2") (pin "15") (pinfunction "LGK_15") (pintype "bidirectional"))
    )
    (net (code "59") (name "/TSENS") (class "Default")
      (node (ref "N1") (pin "9") (pinfunction "TS_9") (pintype "bidirectional"))
      (node (ref "R18") (pin "1") (pinfunction "1_1") (pintype "passive"))
      (node (ref "R19") (pin "2") (pinfunction "2_2") (pintype "passive"))
      (node (ref "X17") (pin "1") (pinfunction "1_1") (pintype "passive"))
    )
    (net (code "60") (name "/T_RESET_L") (class "Default")
      (node (ref "D3") (pin "20") (pinfunction "P5.2_20") (pintype "bidirectional"))
      (node (ref "X10") (pin "1") (pinfunction "1_1") (pintype "passive"))
    )
    (net (code "61") (name "/USBDM0") (class "Default")
      (node (ref "A1") (pin "21") (pinfunction "USB_DN_21") (pintype "bidirectional"))
      (node (ref "D4") (pin "25") (pinfunction "DM0_25") (pintype "bidirectional"))
    )
    (net (code "62") (name "/USBDM1") (class "Default")
      (node (ref "D4") (pin "27") (pinfunction "DM1_27") (pintype "bidirectional"))
      (node (ref "X20") (pin "5") (pinfunction "5_5") (pintype "passive"))
    )
    (net (code "63") (name "/USBDM2") (class "Default")
      (node (ref "D4") (pin "2") (pinfunction "DM2_2") (pintype "bidirectional"))
      (node (ref "X4") (pin "U2") (pinfunction "D-_U2") (pintype "bidirectional"))
    )
    (net (code "64") (name "/USBDM3") (class "Default")
      (node (ref "D4") (pin "8") (pinfunction "DM3_8") (pintype "bidirectional"))
      (node (ref "X3") (pin "2") (pinfunction "D-_2") (pintype "bidirectional"))
      (node (ref "X3") (pin "6") (pinfunction "D-_6") (pintype "bidirectional"))
    )
    (net (code "65") (name "/USBDM4") (class "Default")
      (node (ref "D4") (pin "11") (pinfunction "DM4_11") (pintype "bidirectional"))
      (node (ref "X2") (pin "U2") (pinfunction "D-_U2") (pintype "bidirectional"))
    )
    (net (code "66") (name "/USBDP0") (class "Default")
      (node (ref "A1") (pin "20") (pinfunction "USB_DP_20") (pintype "bidirectional"))
      (node (ref "D4") (pin "26") (pinfunction "DP0_26") (pintype "bidirectional"))
    )
    (net (code "67") (name "/USBDP1") (class "Default")
      (node (ref "D4") (pin "28") (pinfunction "DP1_28") (pintype "bidirectional"))
      (node (ref "X20") (pin "6") (pinfunction "6_6") (pintype "passive"))
    )
    (net (code "68") (name "/USBDP2") (class "Default")
      (node (ref "D4") (pin "3") (pinfunction "DP2_3") (pintype "bidirectional"))
      (node (ref "X4") (pin "U3") (pinfunction "D+_U3") (pintype "bidirectional"))
    )
    (net (code "69") (name "/USBDP3") (class "Default")
      (node (ref "D4") (pin "9") (pinfunction "DP3_9") (pintype "bidirectional"))
      (node (ref "X3") (pin "3") (pinfunction "D+_3") (pintype "bidirectional"))
      (node (ref "X3") (pin "7") (pinfunction "D+_7") (pintype "bidirectional"))
    )
    (net (code "70") (name "/USBDP4") (class "Default")
      (node (ref "D4") (pin "12") (pinfunction "DP4_12") (pintype "bidirectional"))
      (node (ref "X2") (pin "U3") (pinfunction "D+_U3") (pintype "bidirectional"))
    )
    (net (code "71") (name "/USB_5V") (class "Default")
      (node (ref "C15") (pin "1") (pinfunction "1_1") (pintype "passive"))
      (node (ref "N1") (pin "22") (pinfunction "USB_22") (pintype "bidirectional"))
      (node (ref "X2") (pin "U1") (pinfunction "VBUS_U1") (pintype "bidirectional"))
      (node (ref "X3") (pin "1") (pinfunction "VCC_1") (pintype "bidirectional"))
      (node (ref "X3") (pin "5") (pinfunction "VCC_5") (pintype "bidirectional"))
      (node (ref "X4") (pin "U1") (pinfunction "VBUS_U1") (pintype "bidirectional"))
      (node (ref "X5") (pin "13") (pinfunction "13_13") (pintype "passive"))
      (node (ref "X6") (pin "13") (pinfunction "13_13") (pintype "passive"))
      (node (ref "X9") (pin "1") (pinfunction "1_1") (pintype "passive"))
    )
    (net (code "72") (name "/VBATTERY") (class "Default")
      (node (ref "C17") (pin "1") (pinfunction "1_1") (pintype "passive"))
      (node (ref "N1") (pin "11") (pinfunction "BAT1_11") (pintype "bidirectional"))
      (node (ref "N1") (pin "12") (pinfunction "BAT2_12") (pintype "bidirectional"))
      (node (ref "X15") (pin "1") (pinfunction "1_1") (pintype "passive"))
    )
    (net (code "73") (name "/VSYS") (class "Default")
      (node (ref "C28") (pin "1") (pinfunction "1_1") (pintype "passive"))
      (node (ref "C35") (pin "1") (pinfunction "1_1") (pintype "passive"))
      (node (ref "D1") (pin "8") (pinfunction "VREGIN_8") (pintype "bidirectional"))
      (node (ref "D4") (pin "23") (pinfunction "V5_23") (pintype "bidirectional"))
      (node (ref "N2") (pin "1") (pinfunction "IN_2_1") (pintype "input"))
      (node (ref "N2") (pin "2") (pinfunction "IN_2") (pintype "input"))
      (node (ref "N2") (pin "4") (pinfunction "BIAS_4") (pintype "power_in"))
      (node (ref "N2") (pin "5") (pinfunction "EN_5") (pintype "input"))
      (node (ref "X19") (pin "1") (pinfunction "1_1") (pintype "passive"))
    )
    (net (code "74") (name "/VSYS_BQOUT") (class "Default")
      (node (ref "C18") (pin "1") (pinfunction "1_1") (pintype "passive"))
      (node (ref "L1") (pin "B") (pinfunction "B_B") (pintype "bidirectional"))
      (node (ref "N1") (pin "13") (pinfunction "SYS1_13") (pintype "bidirectional"))
      (node (ref "N1") (pin "14") (pinfunction "SYS2_14") (pintype "bidirectional"))
      (node (ref "X18") (pin "1") (pinfunction "1_1") (pintype "passive"))
    )
    (net (code "75") (name "/V_DRV") (class "Default")
      (node (ref "C16") (pin "1") (pinfunction "1_1") (pintype "passive"))
      (node (ref "N1") (pin "6") (pinfunction "DRV_6") (pintype "bidirectional"))
      (node (ref "R18") (pin "2") (pinfunction "2_2") (pintype "passive"))
      (node (ref "R9") (pin "1") (pinfunction "1_1") (pintype "passive"))
    )
    (net (code "76") (name "/X11") (class "Default")
      (node (ref "C14") (pin "1") (pinfunction "1_1") (pintype "passive"))
      (node (ref "N1") (pin "21") (pinfunction "IN_21") (pintype "bidirectional"))
      (node (ref "X13") (pin "1") (pinfunction "1_1") (pintype "passive"))
    )
    (net (code "77") (name "GND") (class "Default")
      (node (ref "A1") (pin "22") (pinfunction "GND16_22") (pintype "bidirectional"))
      (node (ref "A1") (pin "25") (pinfunction "GND12_25") (pintype "bidirectional"))
      (node (ref "A1") (pin "27") (pinfunction "GND13_27") (pintype "bidirectional"))
      (node (ref "A1") (pin "28") (pinfunction "GND1_28") (pintype "bidirectional"))
      (node (ref "A1") (pin "29") (pinfunction "GND2_29") (pintype "bidirectional"))
      (node (ref "A1") (pin "30") (pinfunction "GND3_30") (pintype "bidirectional"))
      (node (ref "A1") (pin "31") (pinfunction "GND4_31") (pintype "bidirectional"))
      (node (ref "A1") (pin "32") (pinfunction "GND5_32") (pintype "bidirectional"))
      (node (ref "A1") (pin "34") (pinfunction "GND6_34") (pintype "bidirectional"))
      (node (ref "A1") (pin "42") (pinfunction "GND7_42") (pintype "bidirectional"))
      (node (ref "A1") (pin "45") (pinfunction "GND8_45") (pintype "bidirectional"))
      (node (ref "A1") (pin "46") (pinfunction "GND9_46") (pintype "bidirectional"))
      (node (ref "A1") (pin "47") (pinfunction "GND10_47") (pintype "bidirectional"))
      (node (ref "A1") (pin "48") (pinfunction "GND11_48") (pintype "bidirectional"))
      (node (ref "A1") (pin "49") (pinfunction "GND14_49") (pintype "bidirectional"))
      (node (ref "A1") (pin "7") (pinfunction "GND15_7") (pintype "bidirectional"))
      (node (ref "A2") (pin "1") (pinfunction "GND_1") (pintype "bidirectional"))
      (node (ref "C1") (pin "2") (pinfunction "2_2") (pintype "passive"))
      (node (ref "C12") (pin "2") (pinfunction "2_2") (pintype "passive"))
      (node (ref "C13") (pin "2") (pinfunction "2_2") (pintype "passive"))
      (node (ref "C14") (pin "2") (pinfunction "2_2") (pintype "passive"))
      (node (ref "C15") (pin "2") (pinfunction "2_2") (pintype "passive"))
      (node (ref "C16") (pin "2") (pinfunction "2_2") (pintype "passive"))
      (node (ref "C17") (pin "2") (pinfunction "2_2") (pintype "passive"))
      (node (ref "C18") (pin "2") (pinfunction "2_2") (pintype "passive"))
      (node (ref "C19") (pin "2") (pinfunction "2_2") (pintype "passive"))
      (node (ref "C2") (pin "2") (pinfunction "2_2") (pintype "passive"))
      (node (ref "C20") (pin "2") (pinfunction "2_2") (pintype "passive"))
      (node (ref "C22") (pin "2") (pinfunction "2_2") (pintype "passive"))
      (node (ref "C23") (pin "2") (pinfunction "2_2") (pintype "passive"))
      (node (ref "C24") (pin "2") (pinfunction "2_2") (pintype "passive"))
      (node (ref "C25") (pin "2") (pinfunction "2_2") (pintype "passive"))
      (node (ref "C26") (pin "2") (pinfunction "2_2") (pintype "passive"))
      (node (ref "C27") (pin "2") (pinfunction "2_2") (pintype "passive"))
      (node (ref "C28") (pin "2") (pinfunction "2_2") (pintype "passive"))
      (node (ref "C29") (pin "2") (pinfunction "2_2") (pintype "passive"))
      (node (ref "C3") (pin "2") (pinfunction "2_2") (pintype "passive"))
      (node (ref "C30") (pin "2") (pinfunction "2_2") (pintype "passive"))
      (node (ref "C31") (pin "2") (pinfunction "2_2") (pintype "passive"))
      (node (ref "C32") (pin "2") (pinfunction "2_2") (pintype "passive"))
      (node (ref "C34") (pin "2") (pinfunction "2_2") (pintype "passive"))
      (node (ref "C35") (pin "2") (pinfunction "2_2") (pintype "passive"))
      (node (ref "C4") (pin "2") (pinfunction "2_2") (pintype "passive"))
      (node (ref "C5") (pin "2") (pinfunction "2_2") (pintype "passive"))
      (node (ref "C6") (pin "2") (pinfunction "2_2") (pintype "passive"))
      (node (ref "C7") (pin "2") (pinfunction "2_2") (pintype "passive"))
      (node (ref "C8") (pin "1") (pinfunction "1_1") (pintype "passive"))
      (node (ref "C9") (pin "1") (pinfunction "1_1") (pintype "passive"))
      (node (ref "D1") (pin "15") (pinfunction "VREFL_15") (pintype "bidirectional"))
      (node (ref "D1") (pin "16") (pinfunction "VSSA_16") (pintype "bidirectional"))
      (node (ref "D1") (pin "31") (pinfunction "VSS2_31") (pintype "bidirectional"))
      (node (ref "D1") (pin "4") (pinfunction "VSS1_4") (pintype "bidirectional"))
      (node (ref "D1") (pin "47") (pinfunction "VSS3_47") (pintype "bidirectional"))
      (node (ref "D2") (pin "15") (pinfunction "GND_15") (pintype "power_in"))
      (node (ref "D3") (pin "17") (pinfunction "VSS_17") (pintype "bidirectional"))
      (node (ref "D3") (pin "25") (pinfunction "P2.5_25") (pintype "bidirectional"))
      (node (ref "D3") (pin "47") (pinfunction "P1.4_47") (pintype "bidirectional"))
      (node (ref "D3") (pin "5") (pinfunction "AVSS_5") (pintype "bidirectional"))
      (node (ref "D4") (pin "14") (pinfunction "TEST_14") (pintype "bidirectional"))
      (node (ref "D4") (pin "15") (pinfunction "GND_15") (pintype "bidirectional"))
      (node (ref "D5") (pin "4") (pinfunction "GND_4") (pintype "bidirectional"))
      (node (ref "D5") (pin "5") (pinfunction "A2_5") (pintype "bidirectional"))
      (node (ref "D5") (pin "6") (pinfunction "A1_6") (pintype "bidirectional"))
      (node (ref "D5") (pin "7") (pinfunction "A0_7") (pintype "bidirectional"))
      (node (ref "D6") (pin "P10") (pinfunction "GND_P10") (pintype "bidirectional"))
      (node (ref "D6") (pin "P11") (pinfunction "GND_P11") (pintype "bidirectional"))
      (node (ref "D6") (pin "P7") (pinfunction "GND_P7") (pintype "bidirectional"))
      (node (ref "N1") (pin "15") (pinfunction "PGND1_15") (pintype "bidirectional"))
      (node (ref "N1") (pin "16") (pinfunction "PGND2_16") (pintype "bidirectional"))
      (node (ref "N1") (pin "17") (pinfunction "PGND3_17") (pintype "bidirectional"))
      (node (ref "N1") (pin "2") (pinfunction "PSEL_2") (pintype "bidirectional"))
      (node (ref "N1") (pin "24") (pinfunction "CD_24") (pintype "bidirectional"))
      (node (ref "N1") (pin "25") (pinfunction "PAD_25") (pintype "bidirectional"))
      (node (ref "N1") (pin "5") (pinfunction "GND_5") (pintype "bidirectional"))
      (node (ref "N2") (pin "11") (pinfunction "EPAD_11") (pintype "passive"))
      (node (ref "N2") (pin "6") (pinfunction "GND_6") (pintype "passive"))
      (node (ref "R15") (pin "2") (pinfunction "2_2") (pintype "passive"))
      (node (ref "R17") (pin "1") (pinfunction "1_1") (pintype "passive"))
      (node (ref "R19") (pin "1") (pinfunction "1_1") (pintype "passive"))
      (node (ref "R4") (pin "1") (pinfunction "1_1") (pintype "passive"))
      (node (ref "R5") (pin "1") (pinfunction "1_1") (pintype "passive"))
      (node (ref "V1") (pin "2") (pinfunction "S_2") (pintype "output"))
      (node (ref "X1") (pin "2") (pinfunction "2_2") (pintype "passive"))
      (node (ref "X1") (pin "3") (pinfunction "2_3") (pintype "passive"))
      (node (ref "X1") (pin "4") (pinfunction "2_4") (pintype "passive"))
      (node (ref "X1") (pin "5") (pinfunction "2_5") (pintype "passive"))
      (node (ref "X12") (pin "1") (pinfunction "1_1") (pintype "passive"))
      (node (ref "X16") (pin "1") (pinfunction "1_1") (pintype "passive"))
      (node (ref "X2") (pin "13") (pinfunction "LYK_13") (pintype "bidirectional"))
      (node (ref "X2") (pin "S1") (pinfunction "S1_S1") (pintype "bidirectional"))
      (node (ref "X2") (pin "S2") (pinfunction "S2_S2") (pintype "bidirectional"))
      (node (ref "X2") (pin "S3") (pinfunction "S3_S3") (pintype "bidirectional"))
      (node (ref "X2") (pin "S4") (pinfunction "S4_S4") (pintype "bidirectional"))
      (node (ref "X2") (pin "S5") (pinfunction "S5_S5") (pintype "bidirectional"))
      (node (ref "X2") (pin "S6") (pinfunction "S6_S6") (pintype "bidirectional"))
      (node (ref "X2") (pin "U4") (pinfunction "GND_U4") (pintype "bidirectional"))
      (node (ref "X3") (pin "4") (pinfunction "GND_4") (pintype "bidirectional"))
      (node (ref "X3") (pin "8") (pinfunction "GND_8") (pintype "bidirectional"))
      (node (ref "X3") (pin "P$1") (pinfunction "GND_P$1") (pintype "bidirectional"))
      (node (ref "X3") (pin "P$2") (pinfunction "GND_P$2") (pintype "bidirectional"))
      (node (ref "X4") (pin "13") (pinfunction "LYK_13") (pintype "bidirectional"))
      (node (ref "X4") (pin "S1") (pinfunction "S1_S1") (pintype "bidirectional"))
      (node (ref "X4") (pin "S2") (pinfunction "S2_S2") (pintype "bidirectional"))
      (node (ref "X4") (pin "S3") (pinfunction "S3_S3") (pintype "bidirectional"))
      (node (ref "X4") (pin "S4") (pinfunction "S4_S4") (pintype "bidirectional"))
      (node (ref "X4") (pin "S5") (pinfunction "S5_S5") (pintype "bidirectional"))
      (node (ref "X4") (pin "S6") (pinfunction "S6_S6") (pintype "bidirectional"))
      (node (ref "X4") (pin "U4") (pinfunction "GND_U4") (pintype "bidirectional"))
      (node (ref "X5") (pin "15") (pinfunction "15_15") (pintype "passive"))
      (node (ref "X6") (pin "15") (pinfunction "15_15") (pintype "passive"))
      (node (ref "X7") (pin "3") (pinfunction "3_3") (pintype "passive"))
      (node (ref "X8") (pin "3") (pinfunction "3_3") (pintype "passive"))
      (node (ref "X9") (pin "5") (pinfunction "5_5") (pintype "passive"))
      (node (ref "X9") (pin "Z1") (pinfunction "5_Z1") (pintype "passive"))
      (node (ref "X9") (pin "Z2") (pinfunction "5_Z2") (pintype "passive"))
      (node (ref "X9") (pin "Z3") (pinfunction "5_Z3") (pintype "passive"))
      (node (ref "X9") (pin "Z4") (pinfunction "5_Z4") (pintype "passive"))
    )
    (net (code "78") (name "Net-(A1-ANT0)") (class "Default")
      (node (ref "A1") (pin "26") (pinfunction "ANT0_26") (pintype "bidirectional"))
      (node (ref "R20") (pin "1") (pinfunction "1_1") (pintype "passive"))
      (node (ref "X1") (pin "1") (pinfunction "1_1") (pintype "passive"))
    )
    (net (code "79") (name "Net-(A1-LED0_WLAN)") (class "Default")
      (node (ref "A1") (pin "41") (pinfunction "LED0_WLAN_41") (pintype "bidirectional"))
      (node (ref "H2") (pin "C") (pinfunction "C_C") (pintype "passive"))
    )
    (net (code "80") (name "Net-(A2-LED-)") (class "Default")
      (node (ref "A2") (pin "16") (pinfunction "LED-_16") (pintype "bidirectional"))
      (node (ref "V1") (pin "3") (pinfunction "D_3") (pintype "input"))
    )
    (net (code "81") (name "Net-(D1-PTA0)") (class "Default")
      (node (ref "D1") (pin "22") (pinfunction "PTA0_22") (pintype "bidirectional"))
      (node (ref "D3") (pin "32") (pinfunction "P0.7_32") (pintype "bidirectional"))
    )
    (net (code "82") (name "Net-(D1-PTA1)") (class "Default")
      (node (ref "D1") (pin "23") (pinfunction "PTA1_23") (pintype "bidirectional"))
      (node (ref "D3") (pin "38") (pinfunction "P0.0_38") (pintype "bidirectional"))
    )
    (net (code "83") (name "Net-(D1-PTA2)") (class "Default")
      (node (ref "D1") (pin "24") (pinfunction "PTA2_24") (pintype "bidirectional"))
      (node (ref "D3") (pin "37") (pinfunction "P0.1_37") (pintype "bidirectional"))
    )
    (net (code "84") (name "Net-(D1-PTA3)") (class "Default")
      (node (ref "D1") (pin "25") (pinfunction "PTA3_25") (pintype "bidirectional"))
      (node (ref "D3") (pin "33") (pinfunction "P0.6_33") (pintype "bidirectional"))
      (node (ref "D3") (pin "34") (pinfunction "P0.5_34") (pintype "bidirectional"))
    )
    (net (code "85") (name "Net-(D1-PTA18)") (class "Default")
      (node (ref "D1") (pin "32") (pinfunction "PTA18_32") (pintype "bidirectional"))
      (node (ref "G1") (pin "3") (pinfunction "X2_3") (pintype "bidirectional"))
    )
    (net (code "86") (name "Net-(D1-PTA19)") (class "Default")
      (node (ref "D1") (pin "33") (pinfunction "PTA19_33") (pintype "bidirectional"))
      (node (ref "G1") (pin "1") (pinfunction "X1_1") (pintype "bidirectional"))
    )
    (net (code "87") (name "Net-(D1-RESET_B)") (class "Default")
      (node (ref "D1") (pin "34") (pinfunction "RESET_B_34") (pintype "bidirectional"))
      (node (ref "D3") (pin "8") (pinfunction "P3.2_8") (pintype "bidirectional"))
    )
    (net (code "88") (name "Net-(D1-VREF_OUT)") (class "Default")
      (node (ref "C24") (pin "1") (pinfunction "1_1") (pintype "passive"))
      (node (ref "D1") (pin "17") (pinfunction "VREF_OUT_17") (pintype "bidirectional"))
    )
    (net (code "89") (name "Net-(D2A-C1+)") (class "Default")
      (node (ref "C10") (pin "1") (pinfunction "1_1") (pintype "passive"))
      (node (ref "D2") (pin "1") (pinfunction "C1+_1") (pintype "bidirectional"))
    )
    (net (code "90") (name "Net-(D2A-C1-)") (class "Default")
      (node (ref "C10") (pin "2") (pinfunction "2_2") (pintype "passive"))
      (node (ref "D2") (pin "3") (pinfunction "C1-_3") (pintype "bidirectional"))
    )
    (net (code "91") (name "Net-(D2A-C2+)") (class "Default")
      (node (ref "C11") (pin "2") (pinfunction "2_2") (pintype "passive"))
      (node (ref "D2") (pin "4") (pinfunction "C2+_4") (pintype "bidirectional"))
    )
    (net (code "92") (name "Net-(D2A-C2-)") (class "Default")
      (node (ref "C11") (pin "1") (pinfunction "1_1") (pintype "passive"))
      (node (ref "D2") (pin "5") (pinfunction "C2-_5") (pintype "bidirectional"))
    )
    (net (code "93") (name "Net-(D2A-R2IN)") (class "Default")
      (node (ref "D2") (pin "8") (pinfunction "R2IN_8") (pintype "input"))
      (node (ref "X8") (pin "2") (pinfunction "2_2") (pintype "passive"))
    )
    (net (code "94") (name "Net-(D2A-R2OUT)") (class "Default")
      (node (ref "D2") (pin "9") (pinfunction "R2OUT_9") (pintype "output"))
      (node (ref "R6") (pin "2") (pinfunction "2_2") (pintype "passive"))
    )
    (net (code "95") (name "Net-(D2A-T2OUT)") (class "Default")
      (node (ref "D2") (pin "7") (pinfunction "T2OUT_7") (pintype "output"))
      (node (ref "X8") (pin "1") (pinfunction "1_1") (pintype "passive"))
    )
    (net (code "96") (name "Net-(D2A-V+)") (class "Default")
      (node (ref "C13") (pin "1") (pinfunction "1_1") (pintype "passive"))
      (node (ref "D2") (pin "2") (pinfunction "V+_2") (pintype "bidirectional"))
    )
    (net (code "97") (name "Net-(D2A-V-)") (class "Default")
      (node (ref "C12") (pin "1") (pinfunction "1_1") (pintype "passive"))
      (node (ref "D2") (pin "6") (pinfunction "V-_6") (pintype "bidirectional"))
    )
    (net (code "98") (name "Net-(D3-LDOCAP)") (class "Default")
      (node (ref "C1") (pin "1") (pinfunction "1_1") (pintype "passive"))
      (node (ref "D3") (pin "18") (pinfunction "LDOCAP_18") (pintype "bidirectional"))
    )
    (net (code "99") (name "Net-(D4-PGANG)") (class "Default")
      (node (ref "D4") (pin "18") (pinfunction "PGANG_18") (pintype "bidirectional"))
      (node (ref "R5") (pin "2") (pinfunction "2_2") (pintype "passive"))
    )
    (net (code "100") (name "Net-(D4-RREF)") (class "Default")
      (node (ref "D4") (pin "4") (pinfunction "RREF_4") (pintype "bidirectional"))
      (node (ref "R4") (pin "2") (pinfunction "2_2") (pintype "passive"))
    )
    (net (code "101") (name "Net-(D4-X1)") (class "Default")
      (node (ref "C8") (pin "2") (pinfunction "2_2") (pintype "passive"))
      (node (ref "D4") (pin "6") (pinfunction "X1_6") (pintype "bidirectional"))
      (node (ref "G2") (pin "3") (pinfunction "X2_3") (pintype "bidirectional"))
    )
    (net (code "102") (name "Net-(D4-X2)") (class "Default")
      (node (ref "C9") (pin "2") (pinfunction "2_2") (pintype "passive"))
      (node (ref "D4") (pin "7") (pinfunction "X2_7") (pintype "bidirectional"))
      (node (ref "G2") (pin "1") (pinfunction "X1_1") (pintype "bidirectional"))
    )
    (net (code "103") (name "Net-(D6-C1)") (class "Default")
      (node (ref "C34") (pin "1") (pinfunction "1_1") (pintype "passive"))
      (node (ref "D6") (pin "P6") (pinfunction "C1_P6") (pintype "bidirectional"))
    )
    (net (code "104") (name "Net-(D6-SETC)") (class "Default")
      (node (ref "C33") (pin "2") (pinfunction "2_2") (pintype "passive"))
      (node (ref "D6") (pin "P13") (pinfunction "SETC_P13") (pintype "bidirectional"))
    )
    (net (code "105") (name "Net-(D6-SETP)") (class "Default")
      (node (ref "C33") (pin "1") (pinfunction "1_1") (pintype "passive"))
      (node (ref "D6") (pin "P12") (pinfunction "SETP_P12") (pintype "bidirectional"))
    )
    (net (code "106") (name "Net-(E1-RF)") (class "Default")
      (node (ref "E1") (pin "FB") (pinfunction "RF_FB") (pintype "bidirectional"))
      (node (ref "R20") (pin "2") (pinfunction "2_2") (pintype "passive"))
    )
    (net (code "107") (name "Net-(H1-PadA)") (class "Default")
      (node (ref "H1") (pin "A") (pinfunction "A_A") (pintype "passive"))
      (node (ref "R9") (pin "2") (pinfunction "2_2") (pintype "passive"))
    )
    (net (code "108") (name "Net-(H2-PadA)") (class "Default")
      (node (ref "H2") (pin "A") (pinfunction "A_A") (pintype "passive"))
      (node (ref "R23") (pin "2") (pinfunction "2_2") (pintype "passive"))
    )
    (net (code "109") (name "Net-(N1-BOOT)") (class "Default")
      (node (ref "C21") (pin "2") (pinfunction "2_2") (pintype "passive"))
      (node (ref "N1") (pin "19") (pinfunction "BOOT_19") (pintype "bidirectional"))
    )
    (net (code "110") (name "Net-(N1-PMIDI)") (class "Default")
      (node (ref "C20") (pin "1") (pinfunction "1_1") (pintype "passive"))
      (node (ref "N1") (pin "20") (pinfunction "PMIDI_20") (pintype "bidirectional"))
    )
    (net (code "111") (name "Net-(N1-PMIDU)") (class "Default")
      (node (ref "C19") (pin "1") (pinfunction "1_1") (pintype "passive"))
      (node (ref "N1") (pin "23") (pinfunction "PMIDU_23") (pintype "bidirectional"))
    )
    (net (code "112") (name "Net-(N1-STAT#)") (class "Default")
      (node (ref "H1") (pin "C") (pinfunction "C_C") (pintype "passive"))
      (node (ref "N1") (pin "8") (pinfunction "STAT#_8") (pintype "bidirectional"))
    )
    (net (code "113") (name "Net-(N1-SW)") (class "Default")
      (node (ref "C21") (pin "1") (pinfunction "1_1") (pintype "passive"))
      (node (ref "L1") (pin "A") (pinfunction "A_A") (pintype "bidirectional"))
      (node (ref "N1") (pin "18") (pinfunction "SW_18") (pintype "bidirectional"))
    )
    (net (code "114") (name "Net-(N2-FB)") (class "Default")
      (node (ref "N2") (pin "8") (pinfunction "FB_8") (pintype "input"))
      (node (ref "R16") (pin "1") (pinfunction "1_1") (pintype "passive"))
      (node (ref "R17") (pin "2") (pinfunction "2_2") (pintype "passive"))
    )
    (net (code "115") (name "Net-(N2-SS)") (class "Default")
      (node (ref "C30") (pin "1") (pinfunction "1_1") (pintype "passive"))
      (node (ref "N2") (pin "7") (pinfunction "SS_7") (pintype "input"))
    )
    (net (code "116") (name "Net-(X2-LGA)") (class "Default")
      (node (ref "R8") (pin "1") (pinfunction "1_1") (pintype "passive"))
      (node (ref "X2") (pin "16") (pinfunction "LGA_16") (pintype "bidirectional"))
    )
    (net (code "117") (name "Net-(X2-LYA)") (class "Default")
      (node (ref "R2") (pin "1") (pinfunction "1_1") (pintype "passive"))
      (node (ref "X2") (pin "14") (pinfunction "LYA_14") (pintype "bidirectional"))
    )
    (net (code "118") (name "Net-(X4-LGA)") (class "Default")
      (node (ref "R7") (pin "1") (pinfunction "1_1") (pintype "passive"))
      (node (ref "X4") (pin "16") (pinfunction "LGA_16") (pintype "bidirectional"))
    )
    (net (code "119") (name "Net-(X4-LYA)") (class "Default")
      (node (ref "R3") (pin "1") (pinfunction "1_1") (pintype "passive"))
      (node (ref "X4") (pin "14") (pinfunction "LYA_14") (pintype "bidirectional"))
    )
    (net (code "120") (name "VDD") (class "Default")
      (node (ref "A1") (pin "52") (pinfunction "+2VD_52") (pintype "bidirectional"))
      (node (ref "C4") (pin "1") (pinfunction "1_1") (pintype "passive"))
      (node (ref "C5") (pin "1") (pinfunction "1_1") (pintype "passive"))
      (node (ref "X2") (pin "1") (pinfunction "TCT_1") (pintype "bidirectional"))
      (node (ref "X2") (pin "6") (pinfunction "RCT_6") (pintype "bidirectional"))
      (node (ref "X4") (pin "1") (pinfunction "TCT_1") (pintype "bidirectional"))
      (node (ref "X4") (pin "6") (pinfunction "RCT_6") (pintype "bidirectional"))
    )
    (net (code "121") (name "unconnected-(A1-GPIO11-Pad23)") (class "Default")
      (node (ref "A1") (pin "23") (pinfunction "GPIO11_23") (pintype "bidirectional"))
    )
    (net (code "122") (name "unconnected-(A1-GPIO12-Pad24)") (class "Default")
      (node (ref "A1") (pin "24") (pinfunction "GPIO12_24") (pintype "bidirectional"))
    )
    (net (code "123") (name "unconnected-(A1-GPIO18-Pad6)") (class "Default")
      (node (ref "A1") (pin "6") (pinfunction "GPIO18_6") (pintype "bidirectional"))
    )
    (net (code "124") (name "unconnected-(A1-GPIO19-Pad5)") (class "Default")
      (node (ref "A1") (pin "5") (pinfunction "GPIO19_5") (pintype "bidirectional"))
    )
    (net (code "125") (name "unconnected-(A1-GPIO20-Pad4)") (class "Default")
      (node (ref "A1") (pin "4") (pinfunction "GPIO20_4") (pintype "bidirectional"))
    )
    (net (code "126") (name "unconnected-(A1-GPIO21-Pad3)") (class "Default")
      (node (ref "A1") (pin "3") (pinfunction "GPIO21_3") (pintype "bidirectional"))
    )
    (net (code "127") (name "unconnected-(A1-GPIO22-Pad2)") (class "Default")
      (node (ref "A1") (pin "2") (pinfunction "GPIO22_2") (pintype "bidirectional"))
    )
    (net (code "128") (name "unconnected-(A1-GPIO23-Pad1)") (class "Default")
      (node (ref "A1") (pin "1") (pinfunction "GPIO23_1") (pintype "bidirectional"))
    )
    (net (code "129") (name "unconnected-(A1-LED1-Pad40)") (class "Default")
      (node (ref "A1") (pin "40") (pinfunction "LED1_40") (pintype "bidirectional"))
    )
    (net (code "130") (name "unconnected-(A1-LED4-Pad37)") (class "Default")
      (node (ref "A1") (pin "37") (pinfunction "LED4_37") (pintype "bidirectional"))
    )
    (net (code "131") (name "unconnected-(A1-LED5-Pad36)") (class "Default")
      (node (ref "A1") (pin "36") (pinfunction "LED5_36") (pintype "bidirectional"))
    )
    (net (code "132") (name "unconnected-(A1-LED6-Pad35)") (class "Default")
      (node (ref "A1") (pin "35") (pinfunction "LED6_35") (pintype "bidirectional"))
    )
    (net (code "133") (name "unconnected-(A1-SPI_CLK-Pad17)") (class "Default")
      (node (ref "A1") (pin "17") (pinfunction "SPI_CLK_17") (pintype "bidirectional"))
    )
    (net (code "134") (name "unconnected-(A1-SPI_CS-Pad19)") (class "Default")
      (node (ref "A1") (pin "19") (pinfunction "SPI_CS_19") (pintype "bidirectional"))
    )
    (net (code "135") (name "unconnected-(A1-SPI_MISO-Pad18)") (class "Default")
      (node (ref "A1") (pin "18") (pinfunction "SPI_MISO_18") (pintype "bidirectional"))
    )
    (net (code "136") (name "unconnected-(A1-SPI_MOSI-Pad16)") (class "Default")
      (node (ref "A1") (pin "16") (pinfunction "SPI_MOSI_16") (pintype "bidirectional"))
    )
    (net (code "137") (name "unconnected-(A2-NC1-Pad3)") (class "Default")
      (node (ref "A2") (pin "3") (pinfunction "NC1_3") (pintype "bidirectional"))
    )
    (net (code "138") (name "unconnected-(A2-NC2-Pad4)") (class "Default")
      (node (ref "A2") (pin "4") (pinfunction "NC2_4") (pintype "bidirectional"))
    )
    (net (code "139") (name "unconnected-(A2-NC3-Pad5)") (class "Default")
      (node (ref "A2") (pin "5") (pinfunction "NC3_5") (pintype "bidirectional"))
    )
    (net (code "140") (name "unconnected-(A2-SD_CS-Pad14)") (class "Default")
      (node (ref "A2") (pin "14") (pinfunction "SD_CS_14") (pintype "bidirectional"))
    )
    (net (code "141") (name "unconnected-(A2-SD_MISO-Pad12)") (class "Default")
      (node (ref "A2") (pin "12") (pinfunction "SD_MISO_12") (pintype "bidirectional"))
    )
    (net (code "142") (name "unconnected-(A2-SD_MOSI-Pad13)") (class "Default")
      (node (ref "A2") (pin "13") (pinfunction "SD_MOSI_13") (pintype "bidirectional"))
    )
    (net (code "143") (name "unconnected-(A2-SD_SCK-Pad11)") (class "Default")
      (node (ref "A2") (pin "11") (pinfunction "SD_SCK_11") (pintype "bidirectional"))
    )
    (net (code "144") (name "unconnected-(D1-ADC0_DM0-Pad10)") (class "Default")
      (node (ref "D1") (pin "10") (pinfunction "ADC0_DM0_10") (pintype "bidirectional"))
    )
    (net (code "145") (name "unconnected-(D1-ADC0_DM3-Pad12)") (class "Default")
      (node (ref "D1") (pin "12") (pinfunction "ADC0_DM3_12") (pintype "bidirectional"))
    )
    (net (code "146") (name "unconnected-(D1-ADC0_DP0-Pad9)") (class "Default")
      (node (ref "D1") (pin "9") (pinfunction "ADC0_DP0_9") (pintype "bidirectional"))
    )
    (net (code "147") (name "unconnected-(D1-ADC0_DP3-Pad11)") (class "Default")
      (node (ref "D1") (pin "11") (pinfunction "ADC0_DP3_11") (pintype "bidirectional"))
    )
    (net (code "148") (name "unconnected-(D1-CMP1_IN3-Pad18)") (class "Default")
      (node (ref "D1") (pin "18") (pinfunction "CMP1_IN3_18") (pintype "bidirectional"))
    )
    (net (code "149") (name "unconnected-(D1-EXTAL32-Pad20)") (class "Default")
      (node (ref "D1") (pin "20") (pinfunction "EXTAL32_20") (pintype "bidirectional"))
    )
    (net (code "150") (name "unconnected-(D1-XTAL32-Pad19)") (class "Default")
      (node (ref "D1") (pin "19") (pinfunction "XTAL32_19") (pintype "bidirectional"))
    )
    (net (code "151") (name "unconnected-(D4-OC1_N-Pad21)") (class "Default")
      (node (ref "D4") (pin "21") (pinfunction "OC1_N_21") (pintype "bidirectional"))
    )
    (net (code "152") (name "unconnected-(D4-OC2_N-Pad19)") (class "Default")
      (node (ref "D4") (pin "19") (pinfunction "OC2_N_19") (pintype "bidirectional"))
    )
    (net (code "153") (name "unconnected-(D4-PWREN1-Pad22)") (class "Default")
      (node (ref "D4") (pin "22") (pinfunction "PWREN1_22") (pintype "bidirectional"))
    )
    (net (code "154") (name "unconnected-(D4-PWREN2-Pad20)") (class "Default")
      (node (ref "D4") (pin "20") (pinfunction "PWREN2_20") (pintype "bidirectional"))
    )
    (net (code "155") (name "unconnected-(D5-ALERT-Pad3)") (class "Default")
      (node (ref "D5") (pin "3") (pinfunction "ALERT_3") (pintype "bidirectional"))
    )
    (net (code "156") (name "unconnected-(D6-DRDY-PadP9)") (class "Default")
      (node (ref "D6") (pin "P9") (pinfunction "DRDY_P9") (pintype "bidirectional"))
    )
    (net (code "157") (name "unconnected-(D6-INT1-PadP5)") (class "Default")
      (node (ref "D6") (pin "P5") (pinfunction "INT1_P5") (pintype "bidirectional"))
    )
    (net (code "158") (name "unconnected-(D6-INT2-PadP4)") (class "Default")
      (node (ref "D6") (pin "P4") (pinfunction "INT2_P4") (pintype "bidirectional"))
    )
    (net (code "159") (name "unconnected-(N1-BGATE-Pad10)") (class "Default")
      (node (ref "N1") (pin "10") (pinfunction "BGATE_10") (pintype "bidirectional"))
    )
    (net (code "160") (name "unconnected-(X9-Pad4)") (class "Default")
      (node (ref "X9") (pin "4") (pinfunction "4_4") (pintype "passive"))
    )
  )
)
